# 3d_dsn_approx.net
KiCad netlist of a schematic drawn in Altium Designer
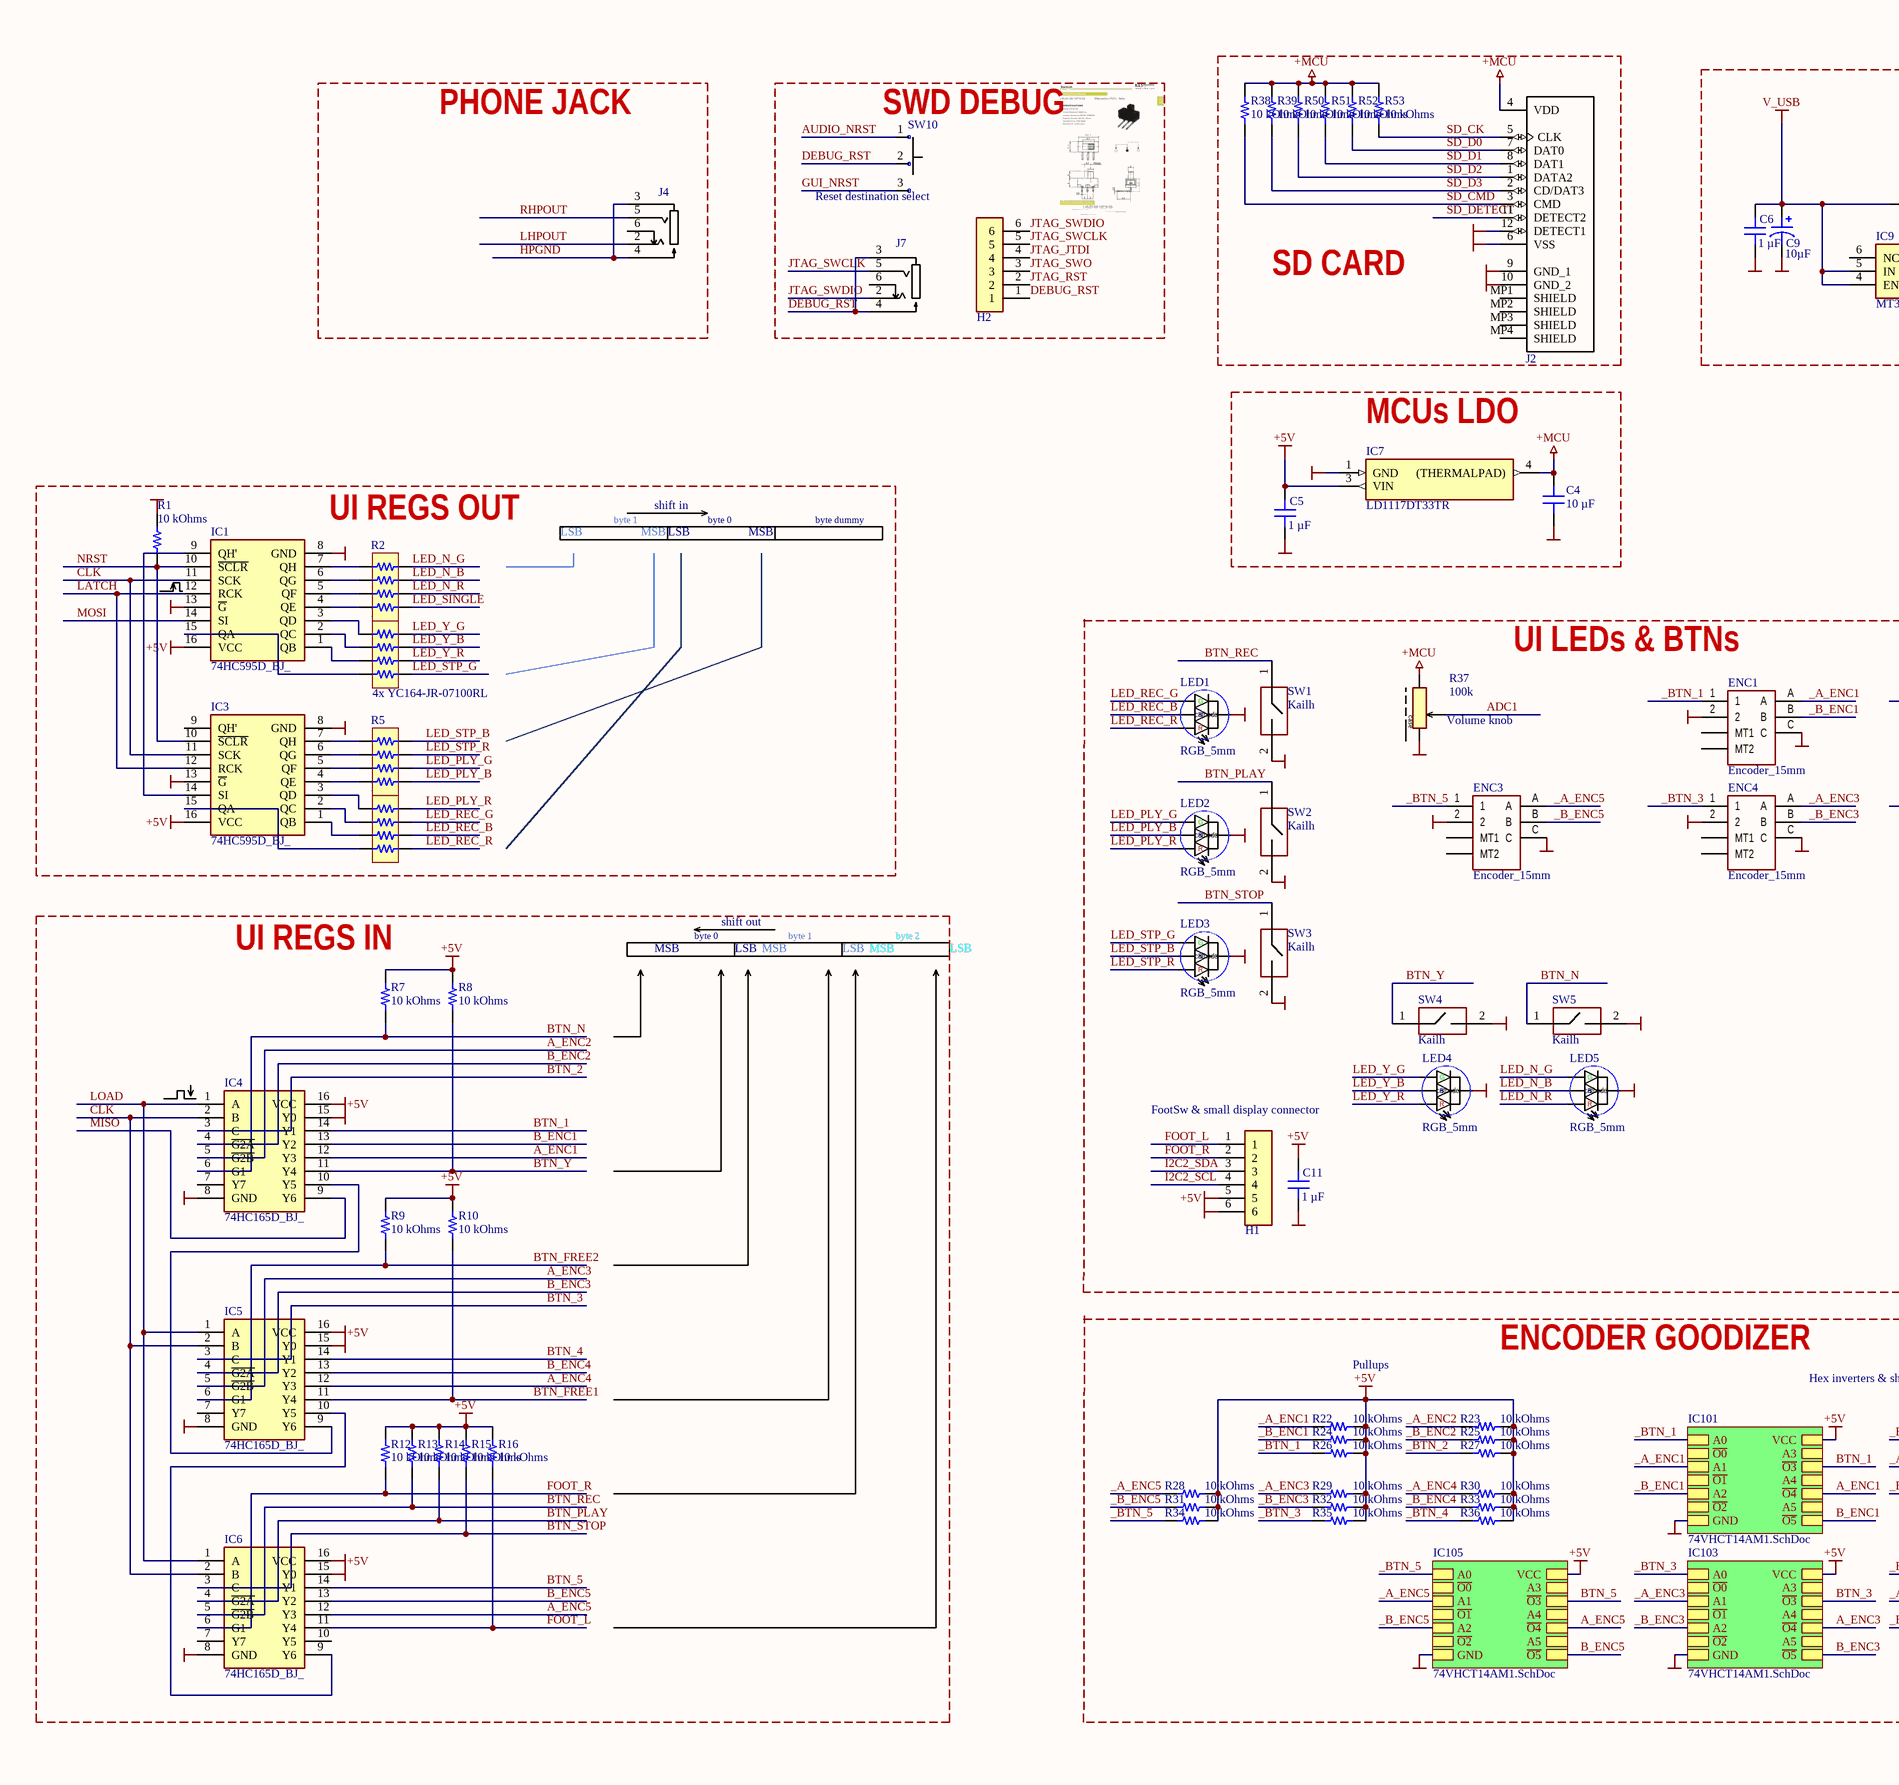
[diagram p0: 3d_dsn_approx.SchDoc, left]
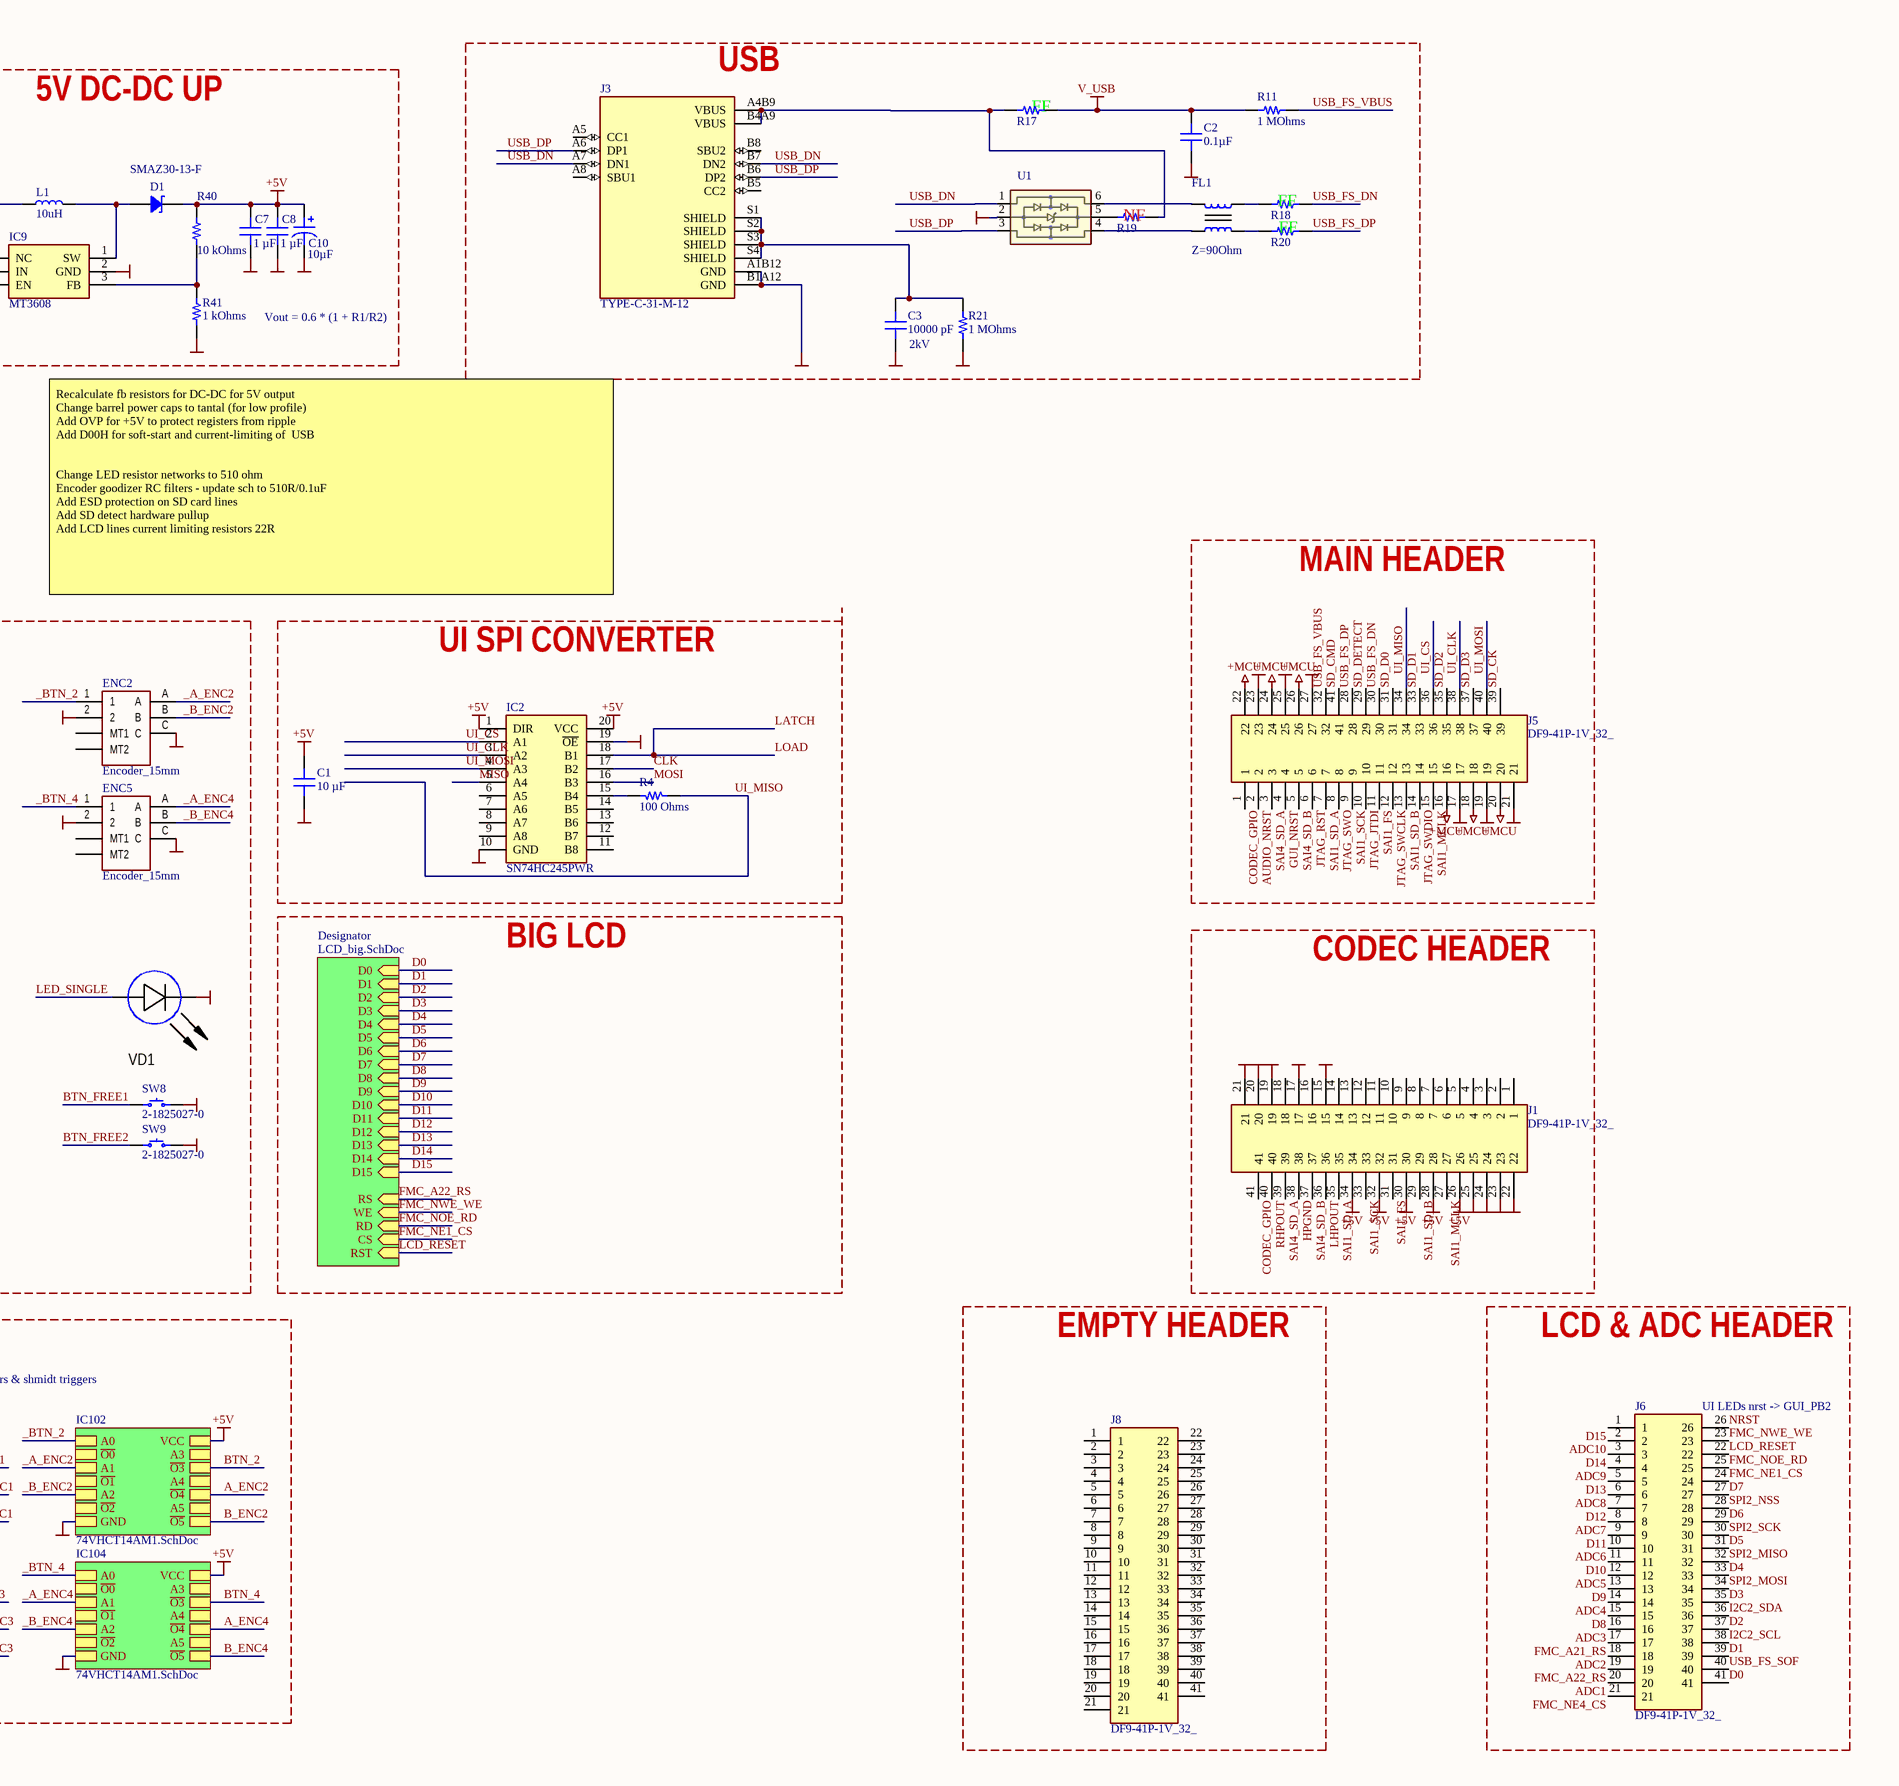
[diagram p1: 3d_dsn_approx.SchDoc, right]

(export (version "E")
  (design (tool "Eeschema 10.0.6"))
  (components
    (comp (ref "C1")
      (value "10 µF")
      (footprint "CAP 0805_2012")
      (description "CAP CER 10UF 10V X5R 0805")
      (fields (field (name "PART NUMBER") "C0805C106K8PAC7800") (field (name "MANUFACTURER") "KEMET"))
      (libsource (lib "Celestial Altium Library - altium_library") (part "Capacitor"))
    )
    (comp (ref "C2")
      (value "0.1µF")
      (footprint "CAP 0402_1005")
      (description "CAP CER 0.1UF 16V X7R 0402")
      (fields (field (name "PART NUMBER") "C0402C104K4RACAUTO") (field (name "MANUFACTURER") "KEMET"))
      (libsource (lib "Celestial Altium Library - altium_library") (part "Capacitor"))
    )
    (comp (ref "C3")
      (value "10000 pF")
      (footprint "CAP 1210_3225 - 1MM")
      (description "CAP CER 10000PF 1KV X7R 1210")
      (fields (field (name "PART NUMBER") "C1210C103KDRAC7800") (field (name "MANUFACTURER") "KEMET"))
      (libsource (lib "Celestial Altium Library - altium_library") (part "Capacitor"))
    )
    (comp (ref "C4")
      (value "10 µF")
      (footprint "CAP 0805_2012")
      (description "CAP CER 10UF 10V X5R 0805")
      (fields (field (name "PART NUMBER") "C0805C106K8PAC7800") (field (name "MANUFACTURER") "KEMET"))
      (libsource (lib "Celestial Altium Library - altium_library") (part "Capacitor"))
    )
    (comp (ref "C5")
      (value "1 µF")
      (footprint "CAP 0805_2012")
      (description "CAP CER 1UF 16V X7R 0805")
      (fields (field (name "PART NUMBER") "C0805C105K4RAC7800") (field (name "MANUFACTURER") "KEMET"))
      (libsource (lib "Celestial Altium Library - altium_library") (part "Capacitor"))
    )
    (comp (ref "C6")
      (value "1 µF")
      (footprint "CAP 0805_2012")
      (description "CAP CER 1UF 16V X7R 0805")
      (fields (field (name "PART NUMBER") "C0805C105K4RAC7800") (field (name "MANUFACTURER") "KEMET"))
      (libsource (lib "Celestial Altium Library - altium_library") (part "Capacitor"))
    )
    (comp (ref "C7")
      (value "1 µF")
      (footprint "CAP 0805_2012")
      (description "CAP CER 1UF 16V X7R 0805")
      (fields (field (name "PART NUMBER") "C0805C105K4RAC7800") (field (name "MANUFACTURER") "KEMET"))
      (libsource (lib "Celestial Altium Library - altium_library") (part "Capacitor"))
    )
    (comp (ref "C8")
      (value "1 µF")
      (footprint "CAP 0805_2012")
      (description "CAP CER 1UF 16V X7R 0805")
      (fields (field (name "PART NUMBER") "C0805C105K4RAC7800") (field (name "MANUFACTURER") "KEMET"))
      (libsource (lib "Celestial Altium Library - altium_library") (part "Capacitor"))
    )
    (comp (ref "C9")
      (value "10µF")
      (footprint "CAP ALSMD POLY 4.3MM H5.5MM")
      (description "CAP ALUM 10UF 20% 35V SMD")
      (fields
        (field (name "PART NUMBER") "EEE-1VA100WR")
        (field (name "MANUFACTURER") "Panasonic Electronic Components")
      )
      (libsource (lib "Celestial Altium Library - altium_library") (part "Polarised Capacitor"))
    )
    (comp (ref "C10")
      (value "10µF")
      (footprint "CAP ALSMD POLY 4.3MM H5.5MM")
      (description "CAP ALUM 10UF 20% 35V SMD")
      (fields
        (field (name "PART NUMBER") "EEE-1VA100WR")
        (field (name "MANUFACTURER") "Panasonic Electronic Components")
      )
      (libsource (lib "Celestial Altium Library - altium_library") (part "Polarised Capacitor"))
    )
    (comp (ref "C11")
      (value "1 µF")
      (footprint "CAP 0805_2012")
      (description "CAP CER 1UF 16V X7R 0805")
      (fields (field (name "PART NUMBER") "C0805C105K4RAC7800") (field (name "MANUFACTURER") "KEMET"))
      (libsource (lib "Celestial Altium Library - altium_library") (part "Capacitor"))
    )
    (comp (ref "D1")
      (value "SMAZ30-13-F")
      (footprint "DO214AC SMA")
      (description "DIODE ZENER 30V 1W SMA")
      (fields (field (name "MANUFACTURER") "Diodes Incorporated") (field (name "TOLERANCE") "±5%"))
      (libsource (lib "Celestial Altium Library - altium_library") (part "Diode Zener"))
    )
    (comp (ref "ENC1")
      (value "Encoder_15mm")
      (footprint "ProtoStack_H750VBT:EC11_15mm")
      (libsource (lib "ProtoStack_H750VBT") (part "Encoder_15mm"))
    )
    (comp (ref "ENC2")
      (value "Encoder_15mm")
      (footprint "ProtoStack_H750VBT:EC11_15mm")
      (libsource (lib "ProtoStack_H750VBT") (part "Encoder_15mm"))
    )
    (comp (ref "ENC3")
      (value "Encoder_15mm")
      (footprint "ProtoStack_H750VBT:EC11_15mm")
      (libsource (lib "ProtoStack_H750VBT") (part "Encoder_15mm"))
    )
    (comp (ref "ENC4")
      (value "Encoder_15mm")
      (footprint "ProtoStack_H750VBT:EC11_15mm")
      (libsource (lib "ProtoStack_H750VBT") (part "Encoder_15mm"))
    )
    (comp (ref "ENC5")
      (value "Encoder_15mm")
      (footprint "ProtoStack_H750VBT:EC11_15mm")
      (libsource (lib "ProtoStack_H750VBT") (part "Encoder_15mm"))
    )
    (comp (ref "FL1")
      (value "Z=90Ohm")
      (footprint "ProtoStack_H750VBT:FIL_ACM2012-361-2P-T002")
      (description "ACM Series 0805 360 Ohm 220mA 500 mOhm DCR 50 V SMT Common Mode Filter")
      (fields (field (name "MP") "ACM2012-361-2P-T002") (field (name "MF") "TDK"))
      (libsource (lib "ProtoStack_H750VBT") (part "ACM2012-361-2P-T002"))
    )
    (comp (ref "H1")
      (value "1.5-6A")
      (footprint "ProtoStack_H750VBT:1.5-6A")
      (description "Pin Header p=1.5mm, 6 pins")
      (libsource (lib "ProtoStack_H750VBT") (part "1.5-6A"))
    )
    (comp (ref "H2")
      (value "1.5-6A")
      (footprint "ProtoStack_H750VBT:1.5-6A")
      (description "Pin Header p=1.5mm, 6 pins")
      (libsource (lib "") (part "1.5-6A_1"))
    )
    (comp (ref "IC1")
      (value "74HC595D_BJ_")
      (footprint "ProtoStack_H750VBT:SOIC127P600X175-16N")
      (description "Integrated Circuit")
      (fields
        (field (name "MANUFACTURER_PART_NUMBER") "74HC595D(BJ)")
        (field (name "MOUSER PART NUMBER") "757-74HC595DBJ")
      )
      (libsource (lib "ProtoStack_H750VBT") (part "74HC595D_BJ_"))
    )
    (comp (ref "IC2")
      (value "SN74HC245PWR")
      (footprint "ProtoStack_H750VBT:SOP65P640X120-20N")
      (description "Integrated Circuit")
      (fields (field (name "MOUSER PART NUMBER") "595-SN74HC245PWR"))
      (libsource (lib "ProtoStack_H750VBT") (part "SN74HC245PWR"))
    )
    (comp (ref "IC3")
      (value "74HC595D_BJ_")
      (footprint "ProtoStack_H750VBT:SOIC127P600X175-16N")
      (description "Integrated Circuit")
      (fields
        (field (name "MANUFACTURER_PART_NUMBER") "74HC595D(BJ)")
        (field (name "MOUSER PART NUMBER") "757-74HC595DBJ")
      )
      (libsource (lib "ProtoStack_H750VBT") (part "74HC595D_BJ_"))
    )
    (comp (ref "IC4")
      (value "74HC165D_BJ_")
      (footprint "ProtoStack_H750VBT:SOIC127P600X175-16N")
      (description "Integrated Circuit")
      (fields
        (field (name "MANUFACTURER_PART_NUMBER") "74HC165D(BJ)")
        (field (name "MOUSER PART NUMBER") "757-74HC165DBJ")
      )
      (libsource (lib "ProtoStack_H750VBT") (part "74HC165D_BJ_"))
    )
    (comp (ref "IC5")
      (value "74HC165D_BJ_")
      (footprint "ProtoStack_H750VBT:SOIC127P600X175-16N")
      (description "Integrated Circuit")
      (fields
        (field (name "MANUFACTURER_PART_NUMBER") "74HC165D(BJ)")
        (field (name "MOUSER PART NUMBER") "757-74HC165DBJ")
      )
      (libsource (lib "ProtoStack_H750VBT") (part "74HC165D_BJ_"))
    )
    (comp (ref "IC6")
      (value "74HC165D_BJ_")
      (footprint "ProtoStack_H750VBT:SOIC127P600X175-16N")
      (description "Integrated Circuit")
      (fields
        (field (name "MANUFACTURER_PART_NUMBER") "74HC165D(BJ)")
        (field (name "MOUSER PART NUMBER") "757-74HC165DBJ")
      )
      (libsource (lib "ProtoStack_H750VBT") (part "74HC165D_BJ_"))
    )
    (comp (ref "IC7")
      (value "LD1117DT33TR")
      (footprint "ProtoStack_H750VBT:TO228P972X240-3N")
      (description "Integrated Circuit")
      (fields (field (name "MOUSER PART NUMBER") "511-LD1117DT33-TR"))
      (libsource (lib "ProtoStack_H750VBT") (part "LD1117DT33TR"))
    )
    (comp (ref "IC9")
      (value "MT3608")
      (footprint "SamacSys:SOT95P280X145-6N")
      (description "Integrated Circuit")
      (libsource (lib "*") (part "MT3608"))
    )
    (comp (ref "J1")
      (value "DF9-41P-1V_32_")
      (footprint "HIROSE_DF9-41P-1V(32)")
      (description "Connector")
      (fields
        (field (name "MANUFACTURER_PART_NUMBER") "DF9-41P-1V(32)")
        (field (name "MOUSER PART NUMBER") "798-DF9-41P-1V32")
      )
      (libsource (lib "") (part "DF9-41P-1V_32__2"))
    )
    (comp (ref "J2")
      (value "SCHA4B0400")
      (footprint "ProtoStack_H750VBT:SCHA4B0400")
      (description "SD card Connector")
      (fields (field (name "MOUSER PART NUMBER") "688-SCHA4B0400"))
      (libsource (lib "ProtoStack_H750VBT") (part "SCHA4B0400"))
    )
    (comp (ref "J3")
      (value "TYPE-C-31-M-12")
      (footprint "ProtoStack_H750VBT:HRO_TYPE-C-31-M-12 - REZONIT")
      (description "USB Connectors 24 Receptacle 1 8.94*7.3mm RoHS")
      (fields (field (name "MF") "{'manufacturer': u'HRO Electronics Co., Ltd.'}"))
      (libsource (lib "ProtoStack_H750VBT") (part "TYPE-C-31-M-12"))
    )
    (comp (ref "J4")
      (value "35RASMT2BHNTRX")
      (footprint "ProtoStack_H750VBT:PJ_327")
      (description "Conn 3.5MM Stereo Jack F 3 POS Solder RA SMD 3 Terminal 1 Port T/R")
      (fields (field (name "MF") "Switchcraft"))
      (libsource (lib "ProtoStack_H750VBT") (part "3.5mm jack stereo smd"))
    )
    (comp (ref "J5")
      (value "DF9-41P-1V_32_")
      (footprint "ProtoStack_H750VBT:HIROSE_DF9-41P-1V(32)")
      (description "Connector")
      (fields
        (field (name "MANUFACTURER_PART_NUMBER") "DF9-41P-1V(32)")
        (field (name "MOUSER PART NUMBER") "798-DF9-41P-1V32")
      )
      (libsource (lib "ProtoStack_H750VBT") (part "DF9-41P-1V_32_"))
    )
    (comp (ref "J6")
      (value "DF9-41P-1V_32_")
      (footprint "ProtoStack_H750VBT:HIROSE_DF9-41P-1V(32)")
      (description "Connector")
      (fields
        (field (name "MANUFACTURER_PART_NUMBER") "DF9-41P-1V(32)")
        (field (name "MOUSER PART NUMBER") "798-DF9-41P-1V32")
      )
      (libsource (lib "") (part "DF9-41P-1V_32__1"))
    )
    (comp (ref "J7")
      (value "35RASMT2BHNTRX")
      (footprint "ProtoStack_H750VBT:PJ_327")
      (description "Conn 3.5MM Stereo Jack F 3 POS Solder RA SMD 3 Terminal 1 Port T/R")
      (fields (field (name "MF") "Switchcraft"))
      (libsource (lib "ProtoStack_H750VBT") (part "3.5mm jack stereo smd"))
    )
    (comp (ref "J8")
      (value "DF9-41P-1V_32_")
      (footprint "ProtoStack_H750VBT:HIROSE_DF9-41P-1V(32)")
      (description "Connector")
      (fields
        (field (name "MANUFACTURER_PART_NUMBER") "DF9-41P-1V(32)")
        (field (name "MOUSER PART NUMBER") "798-DF9-41P-1V32")
      )
      (libsource (lib "") (part "DF9-41P-1V_32__3"))
    )
    (comp (ref "L1")
      (value "10uH")
      (footprint "ProtoStack_H750VBT:IND_CD54")
      (description "Aliexpress CD54 type inductor")
      (libsource (lib "ProtoStack_H750VBT") (part "Inductor_CD54"))
    )
    (comp (ref "LED1")
      (value "RGB_5mm")
      (footprint "ProtoStack_H750VBT:LED_RGB_5MM")
      (libsource (lib "ProtoStack_H750VBT") (part "RGB_CC_5mm"))
    )
    (comp (ref "LED2")
      (value "RGB_5mm")
      (footprint "ProtoStack_H750VBT:LED_RGB_5MM")
      (libsource (lib "ProtoStack_H750VBT") (part "RGB_CC_5mm"))
    )
    (comp (ref "LED3")
      (value "RGB_5mm")
      (footprint "ProtoStack_H750VBT:LED_RGB_5MM")
      (libsource (lib "ProtoStack_H750VBT") (part "RGB_CC_5mm"))
    )
    (comp (ref "LED4")
      (value "RGB_5mm")
      (footprint "ProtoStack_H750VBT:LED_RGB_5MM")
      (libsource (lib "ProtoStack_H750VBT") (part "RGB_CC_5mm"))
    )
    (comp (ref "LED5")
      (value "RGB_5mm")
      (footprint "ProtoStack_H750VBT:LED_RGB_5MM")
      (libsource (lib "ProtoStack_H750VBT") (part "RGB_CC_5mm"))
    )
    (comp (ref "R1")
      (value "10 kOhms")
      (footprint "RES 0603_1608")
      (description "RES SMD 10K OHM 1% 1/10W 0603")
      (fields (field (name "PART NUMBER") "RT0603FRE0710KL") (field (name "MANUFACTURER") "Yageo"))
      (libsource (lib "Celestial Altium Library - altium_library") (part "Resistor"))
    )
    (comp (ref "R2")
      (value "YC164-JR-07100RL")
      (footprint "RESNET 1206-8 CONVEX")
      (description "RES ARRAY 4 RES 100 OHM 1206")
      (fields (field (name "MANUFACTURER") "Yageo") (field (name "TOLERANCE") "±5%"))
      (libsource (lib "Celestial Altium Library - altium_library") (part "Resistor Array (4 circuit)"))
    )
    (comp (ref "R3")
      (value "YC164-JR-07100RL")
      (footprint "RESNET 1206-8 CONVEX")
      (description "RES ARRAY 4 RES 100 OHM 1206")
      (fields (field (name "MANUFACTURER") "Yageo") (field (name "TOLERANCE") "±5%"))
      (libsource (lib "Celestial Altium Library - altium_library") (part "Resistor Array (4 circuit)"))
    )
    (comp (ref "R4")
      (value "100 Ohms")
      (footprint "RES 0402_1005")
      (description "RES SMD 100 OHM 1% 1/16W 0402")
      (fields (field (name "PART NUMBER") "RT0402FRE07100RL") (field (name "MANUFACTURER") "Yageo"))
      (libsource (lib "Celestial Altium Library - altium_library") (part "Resistor"))
    )
    (comp (ref "R5")
      (value "YC164-JR-07100RL")
      (footprint "RESNET 1206-8 CONVEX")
      (description "RES ARRAY 4 RES 100 OHM 1206")
      (fields (field (name "MANUFACTURER") "Yageo") (field (name "TOLERANCE") "±5%"))
      (libsource (lib "Celestial Altium Library - altium_library") (part "Resistor Array (4 circuit)"))
    )
    (comp (ref "R6")
      (value "YC164-JR-07100RL")
      (footprint "RESNET 1206-8 CONVEX")
      (description "RES ARRAY 4 RES 100 OHM 1206")
      (fields (field (name "MANUFACTURER") "Yageo") (field (name "TOLERANCE") "±5%"))
      (libsource (lib "Celestial Altium Library - altium_library") (part "Resistor Array (4 circuit)"))
    )
    (comp (ref "R7")
      (value "10 kOhms")
      (footprint "RES 0603_1608")
      (description "RES SMD 10K OHM 1% 1/10W 0603")
      (fields (field (name "PART NUMBER") "RT0603FRE0710KL") (field (name "MANUFACTURER") "Yageo"))
      (libsource (lib "Celestial Altium Library - altium_library") (part "Resistor"))
    )
    (comp (ref "R8")
      (value "10 kOhms")
      (footprint "RES 0603_1608")
      (description "RES SMD 10K OHM 1% 1/10W 0603")
      (fields (field (name "PART NUMBER") "RT0603FRE0710KL") (field (name "MANUFACTURER") "Yageo"))
      (libsource (lib "Celestial Altium Library - altium_library") (part "Resistor"))
    )
    (comp (ref "R9")
      (value "10 kOhms")
      (footprint "RES 0603_1608")
      (description "RES SMD 10K OHM 1% 1/10W 0603")
      (fields (field (name "PART NUMBER") "RT0603FRE0710KL") (field (name "MANUFACTURER") "Yageo"))
      (libsource (lib "Celestial Altium Library - altium_library") (part "Resistor"))
    )
    (comp (ref "R10")
      (value "10 kOhms")
      (footprint "RES 0603_1608")
      (description "RES SMD 10K OHM 1% 1/10W 0603")
      (fields (field (name "PART NUMBER") "RT0603FRE0710KL") (field (name "MANUFACTURER") "Yageo"))
      (libsource (lib "Celestial Altium Library - altium_library") (part "Resistor"))
    )
    (comp (ref "R11")
      (value "1 MOhms")
      (footprint "RES 0603_1608")
      (description "RES SMD 1M OHM 1% 1/10W 0603")
      (fields (field (name "PART NUMBER") "RT0603FRE071ML") (field (name "MANUFACTURER") "Yageo"))
      (libsource (lib "Celestial Altium Library - altium_library") (part "Resistor"))
    )
    (comp (ref "R12")
      (value "10 kOhms")
      (footprint "RES 0603_1608")
      (description "RES SMD 10K OHM 1% 1/10W 0603")
      (fields (field (name "PART NUMBER") "RT0603FRE0710KL") (field (name "MANUFACTURER") "Yageo"))
      (libsource (lib "Celestial Altium Library - altium_library") (part "Resistor"))
    )
    (comp (ref "R13")
      (value "10 kOhms")
      (footprint "RES 0603_1608")
      (description "RES SMD 10K OHM 1% 1/10W 0603")
      (fields (field (name "PART NUMBER") "RT0603FRE0710KL") (field (name "MANUFACTURER") "Yageo"))
      (libsource (lib "Celestial Altium Library - altium_library") (part "Resistor"))
    )
    (comp (ref "R14")
      (value "10 kOhms")
      (footprint "RES 0603_1608")
      (description "RES SMD 10K OHM 1% 1/10W 0603")
      (fields (field (name "PART NUMBER") "RT0603FRE0710KL") (field (name "MANUFACTURER") "Yageo"))
      (libsource (lib "Celestial Altium Library - altium_library") (part "Resistor"))
    )
    (comp (ref "R15")
      (value "10 kOhms")
      (footprint "RES 0603_1608")
      (description "RES SMD 10K OHM 1% 1/10W 0603")
      (fields (field (name "PART NUMBER") "RT0603FRE0710KL") (field (name "MANUFACTURER") "Yageo"))
      (libsource (lib "Celestial Altium Library - altium_library") (part "Resistor"))
    )
    (comp (ref "R16")
      (value "10 kOhms")
      (footprint "RES 0603_1608")
      (description "RES SMD 10K OHM 1% 1/10W 0603")
      (fields (field (name "PART NUMBER") "RT0603FRE0710KL") (field (name "MANUFACTURER") "Yageo"))
      (libsource (lib "Celestial Altium Library - altium_library") (part "Resistor"))
    )
    (comp (ref "R17")
      (value "~")
      (footprint "RES 0603_1608")
      (description "RES SMD 0 OHM JUMPER 1/10W 0603")
      (fields (field (name "PART NUMBER") "RCA06030000ZSEA") (field (name "MANUFACTURER") "Vishay Dale"))
      (libsource (lib "Celestial Altium Library - altium_library") (part "Resistor"))
    )
    (comp (ref "R18")
      (value "~")
      (footprint "RES 0603_1608")
      (description "RES SMD 0 OHM JUMPER 1/10W 0603")
      (fields (field (name "PART NUMBER") "RCA06030000ZSEA") (field (name "MANUFACTURER") "Vishay Dale"))
      (libsource (lib "Celestial Altium Library - altium_library") (part "Resistor"))
    )
    (comp (ref "R19")
      (value "~")
      (footprint "RES 0603_1608")
      (description "RES SMD 0 OHM JUMPER 1/10W 0603")
      (fields (field (name "PART NUMBER") "RCA06030000ZSEA") (field (name "MANUFACTURER") "Vishay Dale"))
      (libsource (lib "Celestial Altium Library - altium_library") (part "Resistor"))
    )
    (comp (ref "R20")
      (value "~")
      (footprint "RES 0603_1608")
      (description "RES SMD 0 OHM JUMPER 1/10W 0603")
      (fields (field (name "PART NUMBER") "RCA06030000ZSEA") (field (name "MANUFACTURER") "Vishay Dale"))
      (libsource (lib "Celestial Altium Library - altium_library") (part "Resistor"))
    )
    (comp (ref "R21")
      (value "1 MOhms")
      (footprint "RES 0603_1608")
      (description "RES SMD 1M OHM 1% 1/10W 0603")
      (fields (field (name "PART NUMBER") "RT0603FRE071ML") (field (name "MANUFACTURER") "Yageo"))
      (libsource (lib "Celestial Altium Library - altium_library") (part "Resistor"))
    )
    (comp (ref "R22")
      (value "10 kOhms")
      (footprint "RES 0603_1608")
      (description "RES SMD 10K OHM 1% 1/10W 0603")
      (fields (field (name "PART NUMBER") "RT0603FRE0710KL") (field (name "MANUFACTURER") "Yageo"))
      (libsource (lib "Celestial Altium Library - altium_library") (part "Resistor"))
    )
    (comp (ref "R23")
      (value "10 kOhms")
      (footprint "RES 0603_1608")
      (description "RES SMD 10K OHM 1% 1/10W 0603")
      (fields (field (name "PART NUMBER") "RT0603FRE0710KL") (field (name "MANUFACTURER") "Yageo"))
      (libsource (lib "Celestial Altium Library - altium_library") (part "Resistor"))
    )
    (comp (ref "R24")
      (value "10 kOhms")
      (footprint "RES 0603_1608")
      (description "RES SMD 10K OHM 1% 1/10W 0603")
      (fields (field (name "PART NUMBER") "RT0603FRE0710KL") (field (name "MANUFACTURER") "Yageo"))
      (libsource (lib "Celestial Altium Library - altium_library") (part "Resistor"))
    )
    (comp (ref "R25")
      (value "10 kOhms")
      (footprint "RES 0603_1608")
      (description "RES SMD 10K OHM 1% 1/10W 0603")
      (fields (field (name "PART NUMBER") "RT0603FRE0710KL") (field (name "MANUFACTURER") "Yageo"))
      (libsource (lib "Celestial Altium Library - altium_library") (part "Resistor"))
    )
    (comp (ref "R26")
      (value "10 kOhms")
      (footprint "RES 0603_1608")
      (description "RES SMD 10K OHM 1% 1/10W 0603")
      (fields (field (name "PART NUMBER") "RT0603FRE0710KL") (field (name "MANUFACTURER") "Yageo"))
      (libsource (lib "Celestial Altium Library - altium_library") (part "Resistor"))
    )
    (comp (ref "R27")
      (value "10 kOhms")
      (footprint "RES 0603_1608")
      (description "RES SMD 10K OHM 1% 1/10W 0603")
      (fields (field (name "PART NUMBER") "RT0603FRE0710KL") (field (name "MANUFACTURER") "Yageo"))
      (libsource (lib "Celestial Altium Library - altium_library") (part "Resistor"))
    )
    (comp (ref "R28")
      (value "10 kOhms")
      (footprint "RES 0603_1608")
      (description "RES SMD 10K OHM 1% 1/10W 0603")
      (fields (field (name "PART NUMBER") "RT0603FRE0710KL") (field (name "MANUFACTURER") "Yageo"))
      (libsource (lib "Celestial Altium Library - altium_library") (part "Resistor"))
    )
    (comp (ref "R29")
      (value "10 kOhms")
      (footprint "RES 0603_1608")
      (description "RES SMD 10K OHM 1% 1/10W 0603")
      (fields (field (name "PART NUMBER") "RT0603FRE0710KL") (field (name "MANUFACTURER") "Yageo"))
      (libsource (lib "Celestial Altium Library - altium_library") (part "Resistor"))
    )
    (comp (ref "R30")
      (value "10 kOhms")
      (footprint "RES 0603_1608")
      (description "RES SMD 10K OHM 1% 1/10W 0603")
      (fields (field (name "PART NUMBER") "RT0603FRE0710KL") (field (name "MANUFACTURER") "Yageo"))
      (libsource (lib "Celestial Altium Library - altium_library") (part "Resistor"))
    )
    (comp (ref "R31")
      (value "10 kOhms")
      (footprint "RES 0603_1608")
      (description "RES SMD 10K OHM 1% 1/10W 0603")
      (fields (field (name "PART NUMBER") "RT0603FRE0710KL") (field (name "MANUFACTURER") "Yageo"))
      (libsource (lib "Celestial Altium Library - altium_library") (part "Resistor"))
    )
    (comp (ref "R32")
      (value "10 kOhms")
      (footprint "RES 0603_1608")
      (description "RES SMD 10K OHM 1% 1/10W 0603")
      (fields (field (name "PART NUMBER") "RT0603FRE0710KL") (field (name "MANUFACTURER") "Yageo"))
      (libsource (lib "Celestial Altium Library - altium_library") (part "Resistor"))
    )
    (comp (ref "R33")
      (value "10 kOhms")
      (footprint "RES 0603_1608")
      (description "RES SMD 10K OHM 1% 1/10W 0603")
      (fields (field (name "PART NUMBER") "RT0603FRE0710KL") (field (name "MANUFACTURER") "Yageo"))
      (libsource (lib "Celestial Altium Library - altium_library") (part "Resistor"))
    )
    (comp (ref "R34")
      (value "10 kOhms")
      (footprint "RES 0603_1608")
      (description "RES SMD 10K OHM 1% 1/10W 0603")
      (fields (field (name "PART NUMBER") "RT0603FRE0710KL") (field (name "MANUFACTURER") "Yageo"))
      (libsource (lib "Celestial Altium Library - altium_library") (part "Resistor"))
    )
    (comp (ref "R35")
      (value "10 kOhms")
      (footprint "RES 0603_1608")
      (description "RES SMD 10K OHM 1% 1/10W 0603")
      (fields (field (name "PART NUMBER") "RT0603FRE0710KL") (field (name "MANUFACTURER") "Yageo"))
      (libsource (lib "Celestial Altium Library - altium_library") (part "Resistor"))
    )
    (comp (ref "R36")
      (value "10 kOhms")
      (footprint "RES 0603_1608")
      (description "RES SMD 10K OHM 1% 1/10W 0603")
      (fields (field (name "PART NUMBER") "RT0603FRE0710KL") (field (name "MANUFACTURER") "Yageo"))
      (libsource (lib "Celestial Altium Library - altium_library") (part "Resistor"))
    )
    (comp (ref "R37") (value "100k") (footprint "POT") (libsource (lib "Analog") (part "POT 9MM 100K")))
    (comp (ref "R38")
      (value "10 kOhms")
      (footprint "RES 0603_1608")
      (description "RES SMD 10K OHM 1% 1/10W 0603")
      (fields (field (name "PART NUMBER") "RT0603FRE0710KL") (field (name "MANUFACTURER") "Yageo"))
      (libsource (lib "Celestial Altium Library - altium_library") (part "Resistor"))
    )
    (comp (ref "R39")
      (value "10 kOhms")
      (footprint "RES 0603_1608")
      (description "RES SMD 10K OHM 1% 1/10W 0603")
      (fields (field (name "PART NUMBER") "RT0603FRE0710KL") (field (name "MANUFACTURER") "Yageo"))
      (libsource (lib "Celestial Altium Library - altium_library") (part "Resistor"))
    )
    (comp (ref "R40")
      (value "10 kOhms")
      (footprint "RES 0603_1608")
      (description "RES SMD 10K OHM 1% 1/10W 0603")
      (fields (field (name "PART NUMBER") "RT0603FRE0710KL") (field (name "MANUFACTURER") "Yageo"))
      (libsource (lib "Celestial Altium Library - altium_library") (part "Resistor"))
    )
    (comp (ref "R41")
      (value "1 kOhms")
      (footprint "RES 0603_1608")
      (description "RES SMD 1K OHM 1% 1/10W 0603")
      (fields (field (name "PART NUMBER") "RT0603FRE071KL") (field (name "MANUFACTURER") "Yageo"))
      (libsource (lib "Celestial Altium Library - altium_library") (part "Resistor"))
    )
    (comp (ref "R50")
      (value "10 kOhms")
      (footprint "RES 0603_1608")
      (description "RES SMD 10K OHM 1% 1/10W 0603")
      (fields (field (name "PART NUMBER") "RT0603FRE0710KL") (field (name "MANUFACTURER") "Yageo"))
      (libsource (lib "Celestial Altium Library - altium_library") (part "Resistor"))
    )
    (comp (ref "R51")
      (value "10 kOhms")
      (footprint "RES 0603_1608")
      (description "RES SMD 10K OHM 1% 1/10W 0603")
      (fields (field (name "PART NUMBER") "RT0603FRE0710KL") (field (name "MANUFACTURER") "Yageo"))
      (libsource (lib "Celestial Altium Library - altium_library") (part "Resistor"))
    )
    (comp (ref "R52")
      (value "10 kOhms")
      (footprint "RES 0603_1608")
      (description "RES SMD 10K OHM 1% 1/10W 0603")
      (fields (field (name "PART NUMBER") "RT0603FRE0710KL") (field (name "MANUFACTURER") "Yageo"))
      (libsource (lib "Celestial Altium Library - altium_library") (part "Resistor"))
    )
    (comp (ref "R53")
      (value "10 kOhms")
      (footprint "RES 0603_1608")
      (description "RES SMD 10K OHM 1% 1/10W 0603")
      (fields (field (name "PART NUMBER") "RT0603FRE0710KL") (field (name "MANUFACTURER") "Yageo"))
      (libsource (lib "Celestial Altium Library - altium_library") (part "Resistor"))
    )
    (comp (ref "SW1")
      (value "Kailh")
      (footprint "ProtoStack_H750VBT:Kailh_Low")
      (description "Kailh keyboard switch")
      (libsource (lib "ProtoStack_H750VBT") (part "Kailh_SW"))
    )
    (comp (ref "SW2")
      (value "Kailh")
      (footprint "ProtoStack_H750VBT:Kailh_Low")
      (description "Kailh keyboard switch")
      (libsource (lib "ProtoStack_H750VBT") (part "Kailh_SW"))
    )
    (comp (ref "SW3")
      (value "Kailh")
      (footprint "ProtoStack_H750VBT:Kailh_Low")
      (description "Kailh keyboard switch")
      (libsource (lib "ProtoStack_H750VBT") (part "Kailh_SW"))
    )
    (comp (ref "SW4")
      (value "Kailh")
      (footprint "ProtoStack_H750VBT:Kailh_Low")
      (description "Kailh keyboard switch")
      (libsource (lib "") (part "Kailh_SW_1"))
    )
    (comp (ref "SW5")
      (value "Kailh")
      (footprint "ProtoStack_H750VBT:Kailh_Low")
      (description "Kailh keyboard switch")
      (libsource (lib "") (part "Kailh_SW_1"))
    )
    (comp (ref "SW8")
      (value "2-1825027-0")
      (footprint "TE 2-1825027-0")
      (description "SWITCH TACTILE SPST-NO 0.05A 24V")
      (fields (field (name "MANUFACTURER") "TE Connectivity ALCOSWITCH Switches"))
      (libsource (lib "Celestial Altium Library - altium_library") (part "SPST-NO 2 PIN"))
    )
    (comp (ref "SW9")
      (value "2-1825027-0")
      (footprint "TE 2-1825027-0")
      (description "SWITCH TACTILE SPST-NO 0.05A 24V")
      (fields (field (name "MANUFACTURER") "TE Connectivity ALCOSWITCH Switches"))
      (libsource (lib "Celestial Altium Library - altium_library") (part "SPST-NO 2 PIN"))
    )
    (comp (ref "SW10")
      (value "Reset destination select")
      (footprint "ProtoStack_H750VBT:SLIDE_SW_BIG")
      (description "Slide switch")
      (libsource (lib "ProtoStack_H750VBT") (part "RockerSwitch_3mm"))
    )
    (comp (ref "U1")
      (value "~")
      (footprint "SOT-666")
      (description "Very Low Capacitance Esd Protection")
      (fields (field (name "MP") "USBLC6-2") (field (name "MF") "STMicroelectronics"))
      (libsource (lib "ProtoStack_H750VBT") (part "USBLC6-2"))
    )
    (comp (ref "VD1")
      (value "~")
      (footprint "LED: 0805R")
      (fields (field (name "VALUEMANUFACTURERPARTNUMBER") "LED, Green, *, *, *, -55...+150°C"))
      (libsource (lib "diode") (part "LED_single"))
    )
  )
  (nets
    (net (code "1") (name "+5V") (class "Default")
      (node (ref "C1") (pin "2") (pinfunction "2_2") (pintype "passive"))
      (node (ref "C10") (pin "1") (pinfunction "1_1") (pintype "passive"))
      (node (ref "C11") (pin "2") (pinfunction "2_2") (pintype "passive"))
      (node (ref "C5") (pin "2") (pinfunction "2_2") (pintype "passive"))
      (node (ref "C7") (pin "2") (pinfunction "2_2") (pintype "passive"))
      (node (ref "C8") (pin "2") (pinfunction "2_2") (pintype "passive"))
      (node (ref "D1") (pin "2") (pinfunction "2_2") (pintype "passive"))
      (node (ref "H1") (pin "5") (pinfunction "5_5") (pintype "passive"))
      (node (ref "IC1") (pin "16") (pinfunction "VCC_16") (pintype "passive"))
      (node (ref "IC2") (pin "1") (pinfunction "DIR_1") (pintype "passive"))
      (node (ref "IC2") (pin "20") (pinfunction "VCC_20") (pintype "passive"))
      (node (ref "IC3") (pin "16") (pinfunction "VCC_16") (pintype "passive"))
      (node (ref "IC4") (pin "16") (pinfunction "VCC_16") (pintype "passive"))
      (node (ref "IC5") (pin "16") (pinfunction "VCC_16") (pintype "passive"))
      (node (ref "IC6") (pin "16") (pinfunction "VCC_16") (pintype "passive"))
      (node (ref "IC7") (pin "3") (pinfunction "VIN_3") (pintype "output"))
      (node (ref "J1") (pin "26") (pinfunction "26_26") (pintype "passive"))
      (node (ref "J1") (pin "28") (pinfunction "28_28") (pintype "passive"))
      (node (ref "J1") (pin "30") (pinfunction "30_30") (pintype "passive"))
      (node (ref "J1") (pin "32") (pinfunction "32_32") (pintype "passive"))
      (node (ref "J1") (pin "34") (pinfunction "34_34") (pintype "passive"))
      (node (ref "R10") (pin "2") (pinfunction "2_2") (pintype "passive"))
      (node (ref "R12") (pin "2") (pinfunction "2_2") (pintype "passive"))
      (node (ref "R13") (pin "2") (pinfunction "2_2") (pintype "passive"))
      (node (ref "R14") (pin "2") (pinfunction "2_2") (pintype "passive"))
      (node (ref "R15") (pin "2") (pinfunction "2_2") (pintype "passive"))
      (node (ref "R16") (pin "2") (pinfunction "2_2") (pintype "passive"))
      (node (ref "R22") (pin "2") (pinfunction "2_2") (pintype "passive"))
      (node (ref "R23") (pin "2") (pinfunction "2_2") (pintype "passive"))
      (node (ref "R24") (pin "2") (pinfunction "2_2") (pintype "passive"))
      (node (ref "R25") (pin "2") (pinfunction "2_2") (pintype "passive"))
      (node (ref "R26") (pin "2") (pinfunction "2_2") (pintype "passive"))
      (node (ref "R27") (pin "2") (pinfunction "2_2") (pintype "passive"))
      (node (ref "R28") (pin "2") (pinfunction "2_2") (pintype "passive"))
      (node (ref "R29") (pin "2") (pinfunction "2_2") (pintype "passive"))
      (node (ref "R30") (pin "2") (pinfunction "2_2") (pintype "passive"))
      (node (ref "R31") (pin "2") (pinfunction "2_2") (pintype "passive"))
      (node (ref "R32") (pin "2") (pinfunction "2_2") (pintype "passive"))
      (node (ref "R33") (pin "2") (pinfunction "2_2") (pintype "passive"))
      (node (ref "R34") (pin "2") (pinfunction "2_2") (pintype "passive"))
      (node (ref "R35") (pin "2") (pinfunction "2_2") (pintype "passive"))
      (node (ref "R36") (pin "2") (pinfunction "2_2") (pintype "passive"))
      (node (ref "R40") (pin "2") (pinfunction "2_2") (pintype "passive"))
      (node (ref "R7") (pin "2") (pinfunction "2_2") (pintype "passive"))
      (node (ref "R8") (pin "2") (pinfunction "2_2") (pintype "passive"))
      (node (ref "R9") (pin "2") (pinfunction "2_2") (pintype "passive"))
    )
    (net (code "2") (name "+MCU") (class "Default")
      (node (ref "C4") (pin "2") (pinfunction "2_2") (pintype "passive"))
      (node (ref "IC7") (pin "4") (pinfunction "(THERMALPAD)_4") (pintype "output"))
      (node (ref "J2") (pin "4") (pinfunction "VDD_4") (pintype "power_in"))
      (node (ref "J5") (pin "16") (pinfunction "16_16") (pintype "passive"))
      (node (ref "J5") (pin "18") (pinfunction "18_18") (pintype "passive"))
      (node (ref "J5") (pin "20") (pinfunction "20_20") (pintype "passive"))
      (node (ref "J5") (pin "22") (pinfunction "22_22") (pintype "passive"))
      (node (ref "J5") (pin "24") (pinfunction "24_24") (pintype "passive"))
      (node (ref "J5") (pin "26") (pinfunction "26_26") (pintype "passive"))
      (node (ref "R37") (pin "1") (pinfunction "1_1") (pintype "passive"))
      (node (ref "R38") (pin "2") (pinfunction "2_2") (pintype "passive"))
      (node (ref "R39") (pin "2") (pinfunction "2_2") (pintype "passive"))
      (node (ref "R50") (pin "2") (pinfunction "2_2") (pintype "passive"))
      (node (ref "R51") (pin "2") (pinfunction "2_2") (pintype "passive"))
      (node (ref "R52") (pin "2") (pinfunction "2_2") (pintype "passive"))
      (node (ref "R53") (pin "2") (pinfunction "2_2") (pintype "passive"))
    )
    (net (code "18") (name "/ADC1") (class "Default")
      (node (ref "J6") (pin "20") (pinfunction "20_20") (pintype "passive"))
      (node (ref "R37") (pin "2") (pinfunction "2_2") (pintype "passive"))
    )
    (net (code "19") (name "/ADC2") (class "Default")
      (node (ref "J6") (pin "18") (pinfunction "18_18") (pintype "passive"))
    )
    (net (code "20") (name "/ADC3") (class "Default")
      (node (ref "J6") (pin "16") (pinfunction "16_16") (pintype "passive"))
    )
    (net (code "21") (name "/ADC4") (class "Default")
      (node (ref "J6") (pin "14") (pinfunction "14_14") (pintype "passive"))
    )
    (net (code "22") (name "/ADC5") (class "Default")
      (node (ref "J6") (pin "12") (pinfunction "12_12") (pintype "passive"))
    )
    (net (code "23") (name "/ADC6") (class "Default")
      (node (ref "J6") (pin "10") (pinfunction "10_10") (pintype "passive"))
    )
    (net (code "24") (name "/ADC7") (class "Default")
      (node (ref "J6") (pin "8") (pinfunction "8_8") (pintype "passive"))
    )
    (net (code "25") (name "/ADC8") (class "Default")
      (node (ref "J6") (pin "6") (pinfunction "6_6") (pintype "passive"))
    )
    (net (code "26") (name "/ADC9") (class "Default")
      (node (ref "J6") (pin "4") (pinfunction "4_4") (pintype "passive"))
    )
    (net (code "27") (name "/ADC10") (class "Default")
      (node (ref "J6") (pin "2") (pinfunction "2_2") (pintype "passive"))
    )
    (net (code "28") (name "/AUDIO_NRST") (class "Default")
      (node (ref "J5") (pin "2") (pinfunction "2_2") (pintype "passive"))
      (node (ref "SW10") (pin "1") (pinfunction "1_1") (pintype "passive"))
    )
    (net (code "29") (name "/A_ENC1") (class "Default")
      (node (ref "IC4") (pin "12") (pinfunction "Y3_12") (pintype "passive"))
    )
    (net (code "30") (name "/A_ENC2") (class "Default")
      (node (ref "IC4") (pin "5") (pinfunction "~{G2B}_5") (pintype "passive"))
    )
    (net (code "31") (name "/A_ENC3") (class "Default")
      (node (ref "IC5") (pin "5") (pinfunction "~{G2B}_5") (pintype "passive"))
    )
    (net (code "32") (name "/A_ENC4") (class "Default")
      (node (ref "IC5") (pin "12") (pinfunction "Y3_12") (pintype "passive"))
    )
    (net (code "33") (name "/A_ENC5") (class "Default")
      (node (ref "IC6") (pin "12") (pinfunction "Y3_12") (pintype "passive"))
    )
    (net (code "34") (name "/BTN_1") (class "Default")
      (node (ref "IC4") (pin "14") (pinfunction "Y1_14") (pintype "passive"))
    )
    (net (code "35") (name "/BTN_2") (class "Default")
      (node (ref "IC4") (pin "3") (pinfunction "C_3") (pintype "passive"))
    )
    (net (code "36") (name "/BTN_3") (class "Default")
      (node (ref "IC5") (pin "3") (pinfunction "C_3") (pintype "passive"))
    )
    (net (code "37") (name "/BTN_4") (class "Default")
      (node (ref "IC5") (pin "14") (pinfunction "Y1_14") (pintype "passive"))
    )
    (net (code "38") (name "/BTN_5") (class "Default")
      (node (ref "IC6") (pin "14") (pinfunction "Y1_14") (pintype "passive"))
    )
    (net (code "39") (name "/BTN_FREE1") (class "Default")
      (node (ref "IC5") (pin "11") (pinfunction "Y4_11") (pintype "passive"))
      (node (ref "R10") (pin "1") (pinfunction "1_1") (pintype "passive"))
      (node (ref "SW8") (pin "1") (pinfunction "1_1") (pintype "passive"))
    )
    (net (code "40") (name "/BTN_FREE2") (class "Default")
      (node (ref "IC5") (pin "6") (pinfunction "G1_6") (pintype "passive"))
      (node (ref "R9") (pin "1") (pinfunction "1_1") (pintype "passive"))
      (node (ref "SW9") (pin "1") (pinfunction "1_1") (pintype "passive"))
    )
    (net (code "41") (name "/BTN_N") (class "Default")
      (node (ref "IC4") (pin "6") (pinfunction "G1_6") (pintype "passive"))
      (node (ref "R7") (pin "1") (pinfunction "1_1") (pintype "passive"))
      (node (ref "SW5") (pin "1") (pinfunction "1_1") (pintype "passive"))
    )
    (net (code "42") (name "/BTN_PLAY") (class "Default")
      (node (ref "IC6") (pin "4") (pinfunction "~{G2A}_4") (pintype "passive"))
      (node (ref "R14") (pin "1") (pinfunction "1_1") (pintype "passive"))
      (node (ref "SW2") (pin "1") (pinfunction "1_1") (pintype "passive"))
    )
    (net (code "43") (name "/BTN_REC") (class "Default")
      (node (ref "IC6") (pin "5") (pinfunction "~{G2B}_5") (pintype "passive"))
      (node (ref "R13") (pin "1") (pinfunction "1_1") (pintype "passive"))
      (node (ref "SW1") (pin "1") (pinfunction "1_1") (pintype "passive"))
    )
    (net (code "44") (name "/BTN_STOP") (class "Default")
      (node (ref "IC6") (pin "3") (pinfunction "C_3") (pintype "passive"))
      (node (ref "R15") (pin "1") (pinfunction "1_1") (pintype "passive"))
      (node (ref "SW3") (pin "1") (pinfunction "1_1") (pintype "passive"))
    )
    (net (code "45") (name "/BTN_Y") (class "Default")
      (node (ref "IC4") (pin "11") (pinfunction "Y4_11") (pintype "passive"))
      (node (ref "R8") (pin "1") (pinfunction "1_1") (pintype "passive"))
      (node (ref "SW4") (pin "1") (pinfunction "1_1") (pintype "passive"))
    )
    (net (code "46") (name "/B_ENC1") (class "Default")
      (node (ref "IC4") (pin "13") (pinfunction "Y2_13") (pintype "passive"))
    )
    (net (code "47") (name "/B_ENC2") (class "Default")
      (node (ref "IC4") (pin "4") (pinfunction "~{G2A}_4") (pintype "passive"))
    )
    (net (code "48") (name "/B_ENC3") (class "Default")
      (node (ref "IC5") (pin "4") (pinfunction "~{G2A}_4") (pintype "passive"))
    )
    (net (code "49") (name "/B_ENC4") (class "Default")
      (node (ref "IC5") (pin "13") (pinfunction "Y2_13") (pintype "passive"))
    )
    (net (code "50") (name "/B_ENC5") (class "Default")
      (node (ref "IC6") (pin "13") (pinfunction "Y2_13") (pintype "passive"))
    )
    (net (code "51") (name "/CLK") (class "Default")
      (node (ref "IC1") (pin "11") (pinfunction "SCK_11") (pintype "passive"))
      (node (ref "IC2") (pin "17") (pinfunction "B2_17") (pintype "passive"))
      (node (ref "IC3") (pin "11") (pinfunction "SCK_11") (pintype "passive"))
      (node (ref "IC4") (pin "2") (pinfunction "B_2") (pintype "passive"))
      (node (ref "IC5") (pin "2") (pinfunction "B_2") (pintype "passive"))
      (node (ref "IC6") (pin "2") (pinfunction "B_2") (pintype "passive"))
    )
    (net (code "52") (name "/CODEC_GPIO") (class "Default")
      (node (ref "J1") (pin "41") (pinfunction "41_41") (pintype "passive"))
      (node (ref "J5") (pin "1") (pinfunction "1_1") (pintype "passive"))
    )
    (net (code "53") (name "/D0") (class "Default")
      (node (ref "J6") (pin "41") (pinfunction "41_41") (pintype "passive"))
    )
    (net (code "54") (name "/D1") (class "Default")
      (node (ref "J6") (pin "39") (pinfunction "39_39") (pintype "passive"))
    )
    (net (code "55") (name "/D2") (class "Default")
      (node (ref "J6") (pin "37") (pinfunction "37_37") (pintype "passive"))
    )
    (net (code "56") (name "/D3") (class "Default")
      (node (ref "J6") (pin "35") (pinfunction "35_35") (pintype "passive"))
    )
    (net (code "57") (name "/D4") (class "Default")
      (node (ref "J6") (pin "33") (pinfunction "33_33") (pintype "passive"))
    )
    (net (code "58") (name "/D5") (class "Default")
      (node (ref "J6") (pin "31") (pinfunction "31_31") (pintype "passive"))
    )
    (net (code "59") (name "/D6") (class "Default")
      (node (ref "J6") (pin "29") (pinfunction "29_29") (pintype "passive"))
    )
    (net (code "60") (name "/D7") (class "Default")
      (node (ref "J6") (pin "27") (pinfunction "27_27") (pintype "passive"))
    )
    (net (code "61") (name "/D8") (class "Default")
      (node (ref "J6") (pin "15") (pinfunction "15_15") (pintype "passive"))
    )
    (net (code "62") (name "/D9") (class "Default")
      (node (ref "J6") (pin "13") (pinfunction "13_13") (pintype "passive"))
    )
    (net (code "63") (name "/D10") (class "Default")
      (node (ref "J6") (pin "11") (pinfunction "11_11") (pintype "passive"))
    )
    (net (code "64") (name "/D11") (class "Default")
      (node (ref "J6") (pin "9") (pinfunction "9_9") (pintype "passive"))
    )
    (net (code "65") (name "/D12") (class "Default")
      (node (ref "J6") (pin "7") (pinfunction "7_7") (pintype "passive"))
    )
    (net (code "66") (name "/D13") (class "Default")
      (node (ref "J6") (pin "5") (pinfunction "5_5") (pintype "passive"))
    )
    (net (code "67") (name "/D14") (class "Default")
      (node (ref "J6") (pin "3") (pinfunction "3_3") (pintype "passive"))
    )
    (net (code "68") (name "/D15") (class "Default")
      (node (ref "J6") (pin "1") (pinfunction "1_1") (pintype "passive"))
    )
    (net (code "69") (name "/DEBUG_RST") (class "Default")
      (node (ref "H2") (pin "1") (pinfunction "1_1") (pintype "passive"))
      (node (ref "J7") (pin "3") (pinfunction "1_3") (pintype "passive"))
      (node (ref "J7") (pin "4") (pinfunction "5_4") (pintype "passive"))
      (node (ref "SW10") (pin "2") (pinfunction "2_2") (pintype "passive"))
    )
    (net (code "70") (name "/FMC_A21_RS") (class "Default")
      (node (ref "J6") (pin "17") (pinfunction "17_17") (pintype "passive"))
    )
    (net (code "71") (name "/FMC_A22_RS") (class "Default")
      (node (ref "J6") (pin "19") (pinfunction "19_19") (pintype "passive"))
    )
    (net (code "72") (name "/FMC_NE1_CS") (class "Default")
      (node (ref "J6") (pin "24") (pinfunction "24_24") (pintype "passive"))
    )
    (net (code "73") (name "/FMC_NE4_CS") (class "Default")
      (node (ref "J6") (pin "21") (pinfunction "21_21") (pintype "passive"))
    )
    (net (code "74") (name "/FMC_NOE_RD") (class "Default")
      (node (ref "J6") (pin "25") (pinfunction "25_25") (pintype "passive"))
    )
    (net (code "75") (name "/FMC_NWE_WE") (class "Default")
      (node (ref "J6") (pin "23") (pinfunction "23_23") (pintype "passive"))
    )
    (net (code "76") (name "/FOOT_L") (class "Default")
      (node (ref "H1") (pin "1") (pinfunction "1_1") (pintype "passive"))
      (node (ref "IC6") (pin "11") (pinfunction "Y4_11") (pintype "passive"))
      (node (ref "R16") (pin "1") (pinfunction "1_1") (pintype "passive"))
    )
    (net (code "77") (name "/FOOT_R") (class "Default")
      (node (ref "H1") (pin "2") (pinfunction "2_2") (pintype "passive"))
      (node (ref "IC6") (pin "6") (pinfunction "G1_6") (pintype "passive"))
      (node (ref "R12") (pin "1") (pinfunction "1_1") (pintype "passive"))
    )
    (net (code "78") (name "/GUI_NRST") (class "Default")
      (node (ref "J5") (pin "4") (pinfunction "4_4") (pintype "passive"))
      (node (ref "SW10") (pin "3") (pinfunction "3_3") (pintype "passive"))
    )
    (net (code "79") (name "/HPGND") (class "Default")
      (node (ref "J1") (pin "38") (pinfunction "38_38") (pintype "passive"))
      (node (ref "J4") (pin "3") (pinfunction "1_3") (pintype "passive"))
      (node (ref "J4") (pin "4") (pinfunction "5_4") (pintype "passive"))
    )
    (net (code "80") (name "/I2C2_SCL") (class "Default")
      (node (ref "H1") (pin "4") (pinfunction "4_4") (pintype "passive"))
      (node (ref "J6") (pin "38") (pinfunction "38_38") (pintype "passive"))
    )
    (net (code "81") (name "/I2C2_SDA") (class "Default")
      (node (ref "H1") (pin "3") (pinfunction "3_3") (pintype "passive"))
      (node (ref "J6") (pin "36") (pinfunction "36_36") (pintype "passive"))
    )
    (net (code "82") (name "/JTAG_JTDI") (class "Default")
      (node (ref "H2") (pin "4") (pinfunction "4_4") (pintype "passive"))
      (node (ref "J5") (pin "10") (pinfunction "10_10") (pintype "passive"))
    )
    (net (code "83") (name "/JTAG_RST") (class "Default")
      (node (ref "H2") (pin "2") (pinfunction "2_2") (pintype "passive"))
      (node (ref "J5") (pin "6") (pinfunction "6_6") (pintype "passive"))
    )
    (net (code "84") (name "/JTAG_SWCLK") (class "Default")
      (node (ref "H2") (pin "5") (pinfunction "5_5") (pintype "passive"))
      (node (ref "J5") (pin "12") (pinfunction "12_12") (pintype "passive"))
      (node (ref "J7") (pin "5") (pinfunction "3_5") (pintype "passive"))
    )
    (net (code "85") (name "/JTAG_SWDIO") (class "Default")
      (node (ref "H2") (pin "6") (pinfunction "6_6") (pintype "passive"))
      (node (ref "J5") (pin "14") (pinfunction "14_14") (pintype "passive"))
      (node (ref "J7") (pin "2") (pinfunction "2_2") (pintype "passive"))
    )
    (net (code "86") (name "/JTAG_SWO") (class "Default")
      (node (ref "H2") (pin "3") (pinfunction "3_3") (pintype "passive"))
      (node (ref "J5") (pin "8") (pinfunction "8_8") (pintype "passive"))
    )
    (net (code "87") (name "/LATCH") (class "Default")
      (node (ref "IC1") (pin "12") (pinfunction "RCK_12") (pintype "passive"))
      (node (ref "IC2") (pin "18") (pinfunction "B1_18") (pintype "passive"))
      (node (ref "IC3") (pin "12") (pinfunction "RCK_12") (pintype "passive"))
      (node (ref "IC4") (pin "1") (pinfunction "A_1") (pintype "passive"))
      (node (ref "IC5") (pin "1") (pinfunction "A_1") (pintype "passive"))
      (node (ref "IC6") (pin "1") (pinfunction "A_1") (pintype "passive"))
    )
    (net (code "88") (name "/LCD_RESET") (class "Default")
      (node (ref "J6") (pin "22") (pinfunction "22_22") (pintype "passive"))
    )
    (net (code "89") (name "/LED_N_B") (class "Default")
      (node (ref "LED5") (pin "2") (pinfunction "B_2") (pintype "passive"))
      (node (ref "R2") (pin "3") (pinfunction "3_3") (pintype "passive"))
    )
    (net (code "90") (name "/LED_N_G") (class "Default")
      (node (ref "LED5") (pin "1") (pinfunction "G_1") (pintype "passive"))
      (node (ref "R2") (pin "4") (pinfunction "4_4") (pintype "passive"))
    )
    (net (code "91") (name "/LED_N_R") (class "Default")
      (node (ref "LED5") (pin "4") (pinfunction "R_4") (pintype "passive"))
      (node (ref "R2") (pin "2") (pinfunction "2_2") (pintype "passive"))
    )
    (net (code "92") (name "/LED_PLY_B") (class "Default")
      (node (ref "LED2") (pin "2") (pinfunction "B_2") (pintype "passive"))
      (node (ref "R5") (pin "1") (pinfunction "1_1") (pintype "passive"))
    )
    (net (code "93") (name "/LED_PLY_G") (class "Default")
      (node (ref "LED2") (pin "1") (pinfunction "G_1") (pintype "passive"))
      (node (ref "R5") (pin "2") (pinfunction "2_2") (pintype "passive"))
    )
    (net (code "94") (name "/LED_PLY_R") (class "Default")
      (node (ref "LED2") (pin "4") (pinfunction "R_4") (pintype "passive"))
      (node (ref "R6") (pin "4") (pinfunction "4_4") (pintype "passive"))
    )
    (net (code "95") (name "/LED_REC_B") (class "Default")
      (node (ref "LED1") (pin "2") (pinfunction "B_2") (pintype "passive"))
      (node (ref "R6") (pin "2") (pinfunction "2_2") (pintype "passive"))
    )
    (net (code "96") (name "/LED_REC_G") (class "Default")
      (node (ref "LED1") (pin "1") (pinfunction "G_1") (pintype "passive"))
      (node (ref "R6") (pin "3") (pinfunction "3_3") (pintype "passive"))
    )
    (net (code "97") (name "/LED_REC_R") (class "Default")
      (node (ref "LED1") (pin "4") (pinfunction "R_4") (pintype "passive"))
      (node (ref "R6") (pin "1") (pinfunction "1_1") (pintype "passive"))
    )
    (net (code "98") (name "/LED_SINGLE") (class "Default")
      (node (ref "R2") (pin "1") (pinfunction "1_1") (pintype "passive"))
      (node (ref "VD1") (pin "1") (pinfunction "A_1") (pintype "passive"))
    )
    (net (code "99") (name "/LED_STP_B") (class "Default")
      (node (ref "LED3") (pin "2") (pinfunction "B_2") (pintype "passive"))
      (node (ref "R5") (pin "4") (pinfunction "4_4") (pintype "passive"))
    )
    (net (code "100") (name "/LED_STP_G") (class "Default")
      (node (ref "LED3") (pin "1") (pinfunction "G_1") (pintype "passive"))
      (node (ref "R3") (pin "1") (pinfunction "1_1") (pintype "passive"))
    )
    (net (code "101") (name "/LED_STP_R") (class "Default")
      (node (ref "LED3") (pin "4") (pinfunction "R_4") (pintype "passive"))
      (node (ref "R5") (pin "3") (pinfunction "3_3") (pintype "passive"))
    )
    (net (code "102") (name "/LED_Y_B") (class "Default")
      (node (ref "LED4") (pin "2") (pinfunction "B_2") (pintype "passive"))
      (node (ref "R3") (pin "3") (pinfunction "3_3") (pintype "passive"))
    )
    (net (code "103") (name "/LED_Y_G") (class "Default")
      (node (ref "LED4") (pin "1") (pinfunction "G_1") (pintype "passive"))
      (node (ref "R3") (pin "4") (pinfunction "4_4") (pintype "passive"))
    )
    (net (code "104") (name "/LED_Y_R") (class "Default")
      (node (ref "LED4") (pin "4") (pinfunction "R_4") (pintype "passive"))
      (node (ref "R3") (pin "2") (pinfunction "2_2") (pintype "passive"))
    )
    (net (code "105") (name "/LHPOUT") (class "Default")
      (node (ref "J1") (pin "36") (pinfunction "36_36") (pintype "passive"))
      (node (ref "J4") (pin "2") (pinfunction "2_2") (pintype "passive"))
    )
    (net (code "106") (name "/MISO") (class "Default")
      (node (ref "IC2") (pin "5") (pinfunction "A4_5") (pintype "passive"))
      (node (ref "IC4") (pin "9") (pinfunction "Y6_9") (pintype "passive"))
    )
    (net (code "107") (name "/MOSI") (class "Default")
      (node (ref "IC1") (pin "14") (pinfunction "SI_14") (pintype "passive"))
      (node (ref "IC2") (pin "16") (pinfunction "B3_16") (pintype "passive"))
    )
    (net (code "108") (name "/NRST") (class "Default")
      (node (ref "IC1") (pin "10") (pinfunction "~{SCLR}_10") (pintype "passive"))
      (node (ref "IC3") (pin "10") (pinfunction "~{SCLR}_10") (pintype "passive"))
      (node (ref "J6") (pin "26") (pinfunction "26_26") (pintype "passive"))
      (node (ref "R1") (pin "1") (pinfunction "1_1") (pintype "passive"))
    )
    (net (code "109") (name "/RHPOUT") (class "Default")
      (node (ref "J1") (pin "40") (pinfunction "40_40") (pintype "passive"))
      (node (ref "J4") (pin "5") (pinfunction "3_5") (pintype "passive"))
    )
    (net (code "110") (name "/SAI1_FS") (class "Default")
      (node (ref "J1") (pin "31") (pinfunction "31_31") (pintype "passive"))
      (node (ref "J5") (pin "11") (pinfunction "11_11") (pintype "passive"))
    )
    (net (code "111") (name "/SAI1_MCLK") (class "Default")
      (node (ref "J1") (pin "27") (pinfunction "27_27") (pintype "passive"))
      (node (ref "J5") (pin "15") (pinfunction "15_15") (pintype "passive"))
    )
    (net (code "112") (name "/SAI1_SCK") (class "Default")
      (node (ref "J1") (pin "33") (pinfunction "33_33") (pintype "passive"))
      (node (ref "J5") (pin "9") (pinfunction "9_9") (pintype "passive"))
    )
    (net (code "113") (name "/SAI1_SD_A") (class "Default")
      (node (ref "J1") (pin "35") (pinfunction "35_35") (pintype "passive"))
      (node (ref "J5") (pin "7") (pinfunction "7_7") (pintype "passive"))
    )
    (net (code "114") (name "/SAI1_SD_B") (class "Default")
      (node (ref "J1") (pin "29") (pinfunction "29_29") (pintype "passive"))
      (node (ref "J5") (pin "13") (pinfunction "13_13") (pintype "passive"))
    )
    (net (code "115") (name "/SAI4_SD_A") (class "Default")
      (node (ref "J1") (pin "39") (pinfunction "39_39") (pintype "passive"))
      (node (ref "J5") (pin "3") (pinfunction "3_3") (pintype "passive"))
    )
    (net (code "116") (name "/SAI4_SD_B") (class "Default")
      (node (ref "J1") (pin "37") (pinfunction "37_37") (pintype "passive"))
      (node (ref "J5") (pin "5") (pinfunction "5_5") (pintype "passive"))
    )
    (net (code "117") (name "/SD_CK") (class "Default")
      (node (ref "J2") (pin "5") (pinfunction "CLK_5") (pintype "bidirectional"))
      (node (ref "J5") (pin "39") (pinfunction "39_39") (pintype "passive"))
      (node (ref "R53") (pin "1") (pinfunction "1_1") (pintype "passive"))
    )
    (net (code "118") (name "/SD_CMD") (class "Default")
      (node (ref "J2") (pin "3") (pinfunction "CMD_3") (pintype "bidirectional"))
      (node (ref "J5") (pin "41") (pinfunction "41_41") (pintype "passive"))
      (node (ref "R38") (pin "1") (pinfunction "1_1") (pintype "passive"))
    )
    (net (code "119") (name "/SD_D0") (class "Default")
      (node (ref "J2") (pin "7") (pinfunction "DAT0_7") (pintype "bidirectional"))
      (node (ref "J5") (pin "31") (pinfunction "31_31") (pintype "passive"))
      (node (ref "R52") (pin "1") (pinfunction "1_1") (pintype "passive"))
    )
    (net (code "120") (name "/SD_D1") (class "Default")
      (node (ref "J2") (pin "8") (pinfunction "DAT1_8") (pintype "bidirectional"))
      (node (ref "J5") (pin "33") (pinfunction "33_33") (pintype "passive"))
      (node (ref "R51") (pin "1") (pinfunction "1_1") (pintype "passive"))
    )
    (net (code "121") (name "/SD_D2") (class "Default")
      (node (ref "J2") (pin "1") (pinfunction "DATA2_1") (pintype "bidirectional"))
      (node (ref "J5") (pin "35") (pinfunction "35_35") (pintype "passive"))
      (node (ref "R50") (pin "1") (pinfunction "1_1") (pintype "passive"))
    )
    (net (code "122") (name "/SD_D3") (class "Default")
      (node (ref "J2") (pin "2") (pinfunction "CD/DAT3_2") (pintype "bidirectional"))
      (node (ref "J5") (pin "37") (pinfunction "37_37") (pintype "passive"))
      (node (ref "R39") (pin "1") (pinfunction "1_1") (pintype "passive"))
    )
    (net (code "123") (name "/SD_DETECT") (class "Default")
      (node (ref "J2") (pin "11") (pinfunction "DETECT2_11") (pintype "bidirectional"))
      (node (ref "J5") (pin "29") (pinfunction "29_29") (pintype "passive"))
    )
    (net (code "124") (name "/SPI2_MISO") (class "Default")
      (node (ref "J6") (pin "32") (pinfunction "32_32") (pintype "passive"))
    )
    (net (code "125") (name "/SPI2_MOSI") (class "Default")
      (node (ref "J6") (pin "34") (pinfunction "34_34") (pintype "passive"))
    )
    (net (code "126") (name "/SPI2_NSS") (class "Default")
      (node (ref "J6") (pin "28") (pinfunction "28_28") (pintype "passive"))
    )
    (net (code "127") (name "/SPI2_SCK") (class "Default")
      (node (ref "J6") (pin "30") (pinfunction "30_30") (pintype "passive"))
    )
    (net (code "128") (name "/UI_CLK") (class "Default")
      (node (ref "IC2") (pin "3") (pinfunction "A2_3") (pintype "passive"))
      (node (ref "J5") (pin "38") (pinfunction "38_38") (pintype "passive"))
    )
    (net (code "129") (name "/UI_CS") (class "Default")
      (node (ref "IC2") (pin "2") (pinfunction "A1_2") (pintype "passive"))
      (node (ref "J5") (pin "36") (pinfunction "36_36") (pintype "passive"))
    )
    (net (code "130") (name "/UI_MISO") (class "Default")
      (node (ref "J5") (pin "34") (pinfunction "34_34") (pintype "passive"))
      (node (ref "R4") (pin "1") (pinfunction "1_1") (pintype "passive"))
    )
    (net (code "131") (name "/UI_MOSI") (class "Default")
      (node (ref "IC2") (pin "4") (pinfunction "A3_4") (pintype "passive"))
      (node (ref "J5") (pin "40") (pinfunction "40_40") (pintype "passive"))
    )
    (net (code "132") (name "/USB_DN") (class "Default")
      (node (ref "J3") (pin "A7") (pinfunction "DN1_A7") (pintype "bidirectional"))
      (node (ref "J3") (pin "B7") (pinfunction "DN2_B7") (pintype "bidirectional"))
      (node (ref "U1") (pin "1") (pinfunction "1_1") (pintype "bidirectional"))
    )
    (net (code "133") (name "/USB_DP") (class "Default")
      (node (ref "J3") (pin "A6") (pinfunction "DP1_A6") (pintype "bidirectional"))
      (node (ref "J3") (pin "B6") (pinfunction "DP2_B6") (pintype "bidirectional"))
      (node (ref "U1") (pin "3") (pinfunction "3_3") (pintype "bidirectional"))
    )
    (net (code "134") (name "/USB_FS_DN") (class "Default")
      (node (ref "J5") (pin "30") (pinfunction "30_30") (pintype "passive"))
      (node (ref "R18") (pin "1") (pinfunction "1_1") (pintype "passive"))
    )
    (net (code "135") (name "/USB_FS_DP") (class "Default")
      (node (ref "J5") (pin "28") (pinfunction "28_28") (pintype "passive"))
      (node (ref "R20") (pin "1") (pinfunction "1_1") (pintype "passive"))
    )
    (net (code "136") (name "/USB_FS_SOF") (class "Default")
      (node (ref "J6") (pin "40") (pinfunction "40_40") (pintype "passive"))
    )
    (net (code "137") (name "/USB_FS_VBUS") (class "Default")
      (node (ref "J5") (pin "32") (pinfunction "32_32") (pintype "passive"))
      (node (ref "R11") (pin "1") (pinfunction "1_1") (pintype "passive"))
    )
    (net (code "138") (name "/_A_ENC1") (class "Default")
      (node (ref "ENC1") (pin "A") (pinfunction "A_A") (pintype "passive"))
      (node (ref "R22") (pin "1") (pinfunction "1_1") (pintype "passive"))
    )
    (net (code "139") (name "/_A_ENC2") (class "Default")
      (node (ref "ENC2") (pin "A") (pinfunction "A_A") (pintype "passive"))
      (node (ref "R23") (pin "1") (pinfunction "1_1") (pintype "passive"))
    )
    (net (code "140") (name "/_A_ENC3") (class "Default")
      (node (ref "ENC4") (pin "A") (pinfunction "A_A") (pintype "passive"))
      (node (ref "R29") (pin "1") (pinfunction "1_1") (pintype "passive"))
    )
    (net (code "141") (name "/_A_ENC4") (class "Default")
      (node (ref "ENC5") (pin "A") (pinfunction "A_A") (pintype "passive"))
      (node (ref "R30") (pin "1") (pinfunction "1_1") (pintype "passive"))
    )
    (net (code "142") (name "/_A_ENC5") (class "Default")
      (node (ref "ENC3") (pin "A") (pinfunction "A_A") (pintype "passive"))
      (node (ref "R28") (pin "1") (pinfunction "1_1") (pintype "passive"))
    )
    (net (code "143") (name "/_BTN_1") (class "Default")
      (node (ref "ENC1") (pin "1") (pinfunction "1_1") (pintype "passive"))
      (node (ref "R26") (pin "1") (pinfunction "1_1") (pintype "passive"))
    )
    (net (code "144") (name "/_BTN_2") (class "Default")
      (node (ref "ENC2") (pin "1") (pinfunction "1_1") (pintype "passive"))
      (node (ref "R27") (pin "1") (pinfunction "1_1") (pintype "passive"))
    )
    (net (code "145") (name "/_BTN_3") (class "Default")
      (node (ref "ENC4") (pin "1") (pinfunction "1_1") (pintype "passive"))
      (node (ref "R35") (pin "1") (pinfunction "1_1") (pintype "passive"))
    )
    (net (code "146") (name "/_BTN_4") (class "Default")
      (node (ref "ENC5") (pin "1") (pinfunction "1_1") (pintype "passive"))
      (node (ref "R36") (pin "1") (pinfunction "1_1") (pintype "passive"))
    )
    (net (code "147") (name "/_BTN_5") (class "Default")
      (node (ref "ENC3") (pin "1") (pinfunction "1_1") (pintype "passive"))
      (node (ref "R34") (pin "1") (pinfunction "1_1") (pintype "passive"))
    )
    (net (code "148") (name "/_B_ENC1") (class "Default")
      (node (ref "ENC1") (pin "B") (pinfunction "B_B") (pintype "passive"))
      (node (ref "R24") (pin "1") (pinfunction "1_1") (pintype "passive"))
    )
    (net (code "149") (name "/_B_ENC2") (class "Default")
      (node (ref "ENC2") (pin "B") (pinfunction "B_B") (pintype "passive"))
      (node (ref "R25") (pin "1") (pinfunction "1_1") (pintype "passive"))
    )
    (net (code "150") (name "/_B_ENC3") (class "Default")
      (node (ref "ENC4") (pin "B") (pinfunction "B_B") (pintype "passive"))
      (node (ref "R32") (pin "1") (pinfunction "1_1") (pintype "passive"))
    )
    (net (code "151") (name "/_B_ENC4") (class "Default")
      (node (ref "ENC5") (pin "B") (pinfunction "B_B") (pintype "passive"))
      (node (ref "R33") (pin "1") (pinfunction "1_1") (pintype "passive"))
    )
    (net (code "152") (name "/_B_ENC5") (class "Default")
      (node (ref "ENC3") (pin "B") (pinfunction "B_B") (pintype "passive"))
      (node (ref "R31") (pin "1") (pinfunction "1_1") (pintype "passive"))
    )
    (net (code "168") (name "GND") (class "Default")
      (node (ref "C1") (pin "1") (pinfunction "1_1") (pintype "passive"))
      (node (ref "C10") (pin "2") (pinfunction "2_2") (pintype "passive"))
      (node (ref "C11") (pin "1") (pinfunction "1_1") (pintype "passive"))
      (node (ref "C2") (pin "1") (pinfunction "1_1") (pintype "passive"))
      (node (ref "C3") (pin "1") (pinfunction "1_1") (pintype "passive"))
      (node (ref "C4") (pin "1") (pinfunction "1_1") (pintype "passive"))
      (node (ref "C5") (pin "1") (pinfunction "1_1") (pintype "passive"))
      (node (ref "C6") (pin "1") (pinfunction "1_1") (pintype "passive"))
      (node (ref "C7") (pin "1") (pinfunction "1_1") (pintype "passive"))
      (node (ref "C8") (pin "1") (pinfunction "1_1") (pintype "passive"))
      (node (ref "C9") (pin "2") (pinfunction "2_2") (pintype "passive"))
      (node (ref "ENC1") (pin "2") (pinfunction "2_2") (pintype "passive"))
      (node (ref "ENC1") (pin "C") (pinfunction "C_C") (pintype "passive"))
      (node (ref "ENC2") (pin "2") (pinfunction "2_2") (pintype "passive"))
      (node (ref "ENC2") (pin "C") (pinfunction "C_C") (pintype "passive"))
      (node (ref "ENC3") (pin "2") (pinfunction "2_2") (pintype "passive"))
      (node (ref "ENC3") (pin "C") (pinfunction "C_C") (pintype "passive"))
      (node (ref "ENC4") (pin "2") (pinfunction "2_2") (pintype "passive"))
      (node (ref "ENC4") (pin "C") (pinfunction "C_C") (pintype "passive"))
      (node (ref "ENC5") (pin "2") (pinfunction "2_2") (pintype "passive"))
      (node (ref "ENC5") (pin "C") (pinfunction "C_C") (pintype "passive"))
      (node (ref "H1") (pin "6") (pinfunction "6_6") (pintype "passive"))
      (node (ref "IC1") (pin "13") (pinfunction "~{G}_13") (pintype "passive"))
      (node (ref "IC1") (pin "8") (pinfunction "GND_8") (pintype "passive"))
      (node (ref "IC2") (pin "10") (pinfunction "GND_10") (pintype "passive"))
      (node (ref "IC2") (pin "19") (pinfunction "~{OE}_19") (pintype "passive"))
      (node (ref "IC3") (pin "13") (pinfunction "~{G}_13") (pintype "passive"))
      (node (ref "IC3") (pin "8") (pinfunction "GND_8") (pintype "passive"))
      (node (ref "IC4") (pin "15") (pinfunction "Y0_15") (pintype "passive"))
      (node (ref "IC4") (pin "8") (pinfunction "GND_8") (pintype "passive"))
      (node (ref "IC5") (pin "15") (pinfunction "Y0_15") (pintype "passive"))
      (node (ref "IC5") (pin "8") (pinfunction "GND_8") (pintype "passive"))
      (node (ref "IC6") (pin "15") (pinfunction "Y0_15") (pintype "passive"))
      (node (ref "IC6") (pin "8") (pinfunction "GND_8") (pintype "passive"))
      (node (ref "IC7") (pin "1") (pinfunction "GND_1") (pintype "input"))
      (node (ref "IC9") (pin "2") (pinfunction "GND_2") (pintype "passive"))
      (node (ref "J1") (pin "15") (pinfunction "15_15") (pintype "passive"))
      (node (ref "J1") (pin "17") (pinfunction "17_17") (pintype "passive"))
      (node (ref "J1") (pin "19") (pinfunction "19_19") (pintype "passive"))
      (node (ref "J1") (pin "20") (pinfunction "20_20") (pintype "passive"))
      (node (ref "J1") (pin "21") (pinfunction "21_21") (pintype "passive"))
      (node (ref "J1") (pin "22") (pinfunction "22_22") (pintype "passive"))
      (node (ref "J1") (pin "23") (pinfunction "23_23") (pintype "passive"))
      (node (ref "J1") (pin "24") (pinfunction "24_24") (pintype "passive"))
      (node (ref "J1") (pin "25") (pinfunction "25_25") (pintype "passive"))
      (node (ref "J2") (pin "10") (pinfunction "GND_2_10") (pintype "passive"))
      (node (ref "J2") (pin "12") (pinfunction "DETECT1_12") (pintype "bidirectional"))
      (node (ref "J2") (pin "6") (pinfunction "VSS_6") (pintype "power_in"))
      (node (ref "J2") (pin "9") (pinfunction "GND_1_9") (pintype "passive"))
      (node (ref "J3") (pin "A1B12") (pinfunction "GND_A1B12") (pintype "power_in"))
      (node (ref "J3") (pin "B1A12") (pinfunction "GND_B1A12") (pintype "power_in"))
      (node (ref "J5") (pin "17") (pinfunction "17_17") (pintype "passive"))
      (node (ref "J5") (pin "19") (pinfunction "19_19") (pintype "passive"))
      (node (ref "J5") (pin "21") (pinfunction "21_21") (pintype "passive"))
      (node (ref "J5") (pin "23") (pinfunction "23_23") (pintype "passive"))
      (node (ref "J5") (pin "25") (pinfunction "25_25") (pintype "passive"))
      (node (ref "J5") (pin "27") (pinfunction "27_27") (pintype "passive"))
      (node (ref "LED1") (pin "3") (pinfunction "cathode_3") (pintype "passive"))
      (node (ref "LED2") (pin "3") (pinfunction "cathode_3") (pintype "passive"))
      (node (ref "LED3") (pin "3") (pinfunction "cathode_3") (pintype "passive"))
      (node (ref "LED4") (pin "3") (pinfunction "cathode_3") (pintype "passive"))
      (node (ref "LED5") (pin "3") (pinfunction "cathode_3") (pintype "passive"))
      (node (ref "R1") (pin "2") (pinfunction "2_2") (pintype "passive"))
      (node (ref "R21") (pin "1") (pinfunction "1_1") (pintype "passive"))
      (node (ref "R37") (pin "3") (pinfunction "3_3") (pintype "passive"))
      (node (ref "R41") (pin "1") (pinfunction "1_1") (pintype "passive"))
      (node (ref "SW1") (pin "2") (pinfunction "2_2") (pintype "passive"))
      (node (ref "SW2") (pin "2") (pinfunction "2_2") (pintype "passive"))
      (node (ref "SW3") (pin "2") (pinfunction "2_2") (pintype "passive"))
      (node (ref "SW4") (pin "2") (pinfunction "2_2") (pintype "passive"))
      (node (ref "SW5") (pin "2") (pinfunction "2_2") (pintype "passive"))
      (node (ref "SW8") (pin "2") (pinfunction "2_2") (pintype "passive"))
      (node (ref "SW9") (pin "2") (pinfunction "2_2") (pintype "passive"))
      (node (ref "U1") (pin "2") (pinfunction "2_2") (pintype "power_in"))
      (node (ref "VD1") (pin "2") (pinfunction "C_2") (pintype "passive"))
    )
    (net (code "169") (name "Net-(C3-Pad2)") (class "Default")
      (node (ref "C3") (pin "2") (pinfunction "2_2") (pintype "passive"))
      (node (ref "J3") (pin "S1") (pinfunction "SHIELD_S1") (pintype "passive"))
      (node (ref "J3") (pin "S2") (pinfunction "SHIELD_S2") (pintype "passive"))
      (node (ref "J3") (pin "S3") (pinfunction "SHIELD_S3") (pintype "passive"))
      (node (ref "J3") (pin "S4") (pinfunction "SHIELD_S4") (pintype "passive"))
      (node (ref "R21") (pin "2") (pinfunction "2_2") (pintype "passive"))
    )
    (net (code "170") (name "Net-(FL1-Pad1)") (class "Default")
      (node (ref "FL1") (pin "1") (pinfunction "1_1") (pintype "passive"))
      (node (ref "U1") (pin "6") (pinfunction "6_6") (pintype "bidirectional"))
    )
    (net (code "171") (name "Net-(FL1-Pad2)") (class "Default")
      (node (ref "FL1") (pin "2") (pinfunction "2_2") (pintype "passive"))
      (node (ref "U1") (pin "4") (pinfunction "4_4") (pintype "bidirectional"))
    )
    (net (code "172") (name "Net-(FL1-Pad3)") (class "Default")
      (node (ref "FL1") (pin "3") (pinfunction "3_3") (pintype "passive"))
      (node (ref "R20") (pin "2") (pinfunction "2_2") (pintype "passive"))
    )
    (net (code "173") (name "Net-(FL1-Pad4)") (class "Default")
      (node (ref "FL1") (pin "4") (pinfunction "4_4") (pintype "passive"))
      (node (ref "R18") (pin "2") (pinfunction "2_2") (pintype "passive"))
    )
    (net (code "174") (name "Net-(IC1-QA)") (class "Default")
      (node (ref "IC1") (pin "15") (pinfunction "QA_15") (pintype "passive"))
      (node (ref "R3") (pin "8") (pinfunction "8_8") (pintype "passive"))
    )
    (net (code "175") (name "Net-(IC1-QB)") (class "Default")
      (node (ref "IC1") (pin "1") (pinfunction "QB_1") (pintype "passive"))
      (node (ref "R3") (pin "7") (pinfunction "7_7") (pintype "passive"))
    )
    (net (code "176") (name "Net-(IC1-QC)") (class "Default")
      (node (ref "IC1") (pin "2") (pinfunction "QC_2") (pintype "passive"))
      (node (ref "R3") (pin "6") (pinfunction "6_6") (pintype "passive"))
    )
    (net (code "177") (name "Net-(IC1-QD)") (class "Default")
      (node (ref "IC1") (pin "3") (pinfunction "QD_3") (pintype "passive"))
      (node (ref "R3") (pin "5") (pinfunction "5_5") (pintype "passive"))
    )
    (net (code "178") (name "Net-(IC1-QE)") (class "Default")
      (node (ref "IC1") (pin "4") (pinfunction "QE_4") (pintype "passive"))
      (node (ref "R2") (pin "8") (pinfunction "8_8") (pintype "passive"))
    )
    (net (code "179") (name "Net-(IC1-QF)") (class "Default")
      (node (ref "IC1") (pin "5") (pinfunction "QF_5") (pintype "passive"))
      (node (ref "R2") (pin "7") (pinfunction "7_7") (pintype "passive"))
    )
    (net (code "180") (name "Net-(IC1-QG)") (class "Default")
      (node (ref "IC1") (pin "6") (pinfunction "QG_6") (pintype "passive"))
      (node (ref "R2") (pin "6") (pinfunction "6_6") (pintype "passive"))
    )
    (net (code "181") (name "Net-(IC1-QH')") (class "Default")
      (node (ref "IC1") (pin "9") (pinfunction "QH'_9") (pintype "passive"))
      (node (ref "IC3") (pin "14") (pinfunction "SI_14") (pintype "passive"))
    )
    (net (code "182") (name "Net-(IC1-QH)") (class "Default")
      (node (ref "IC1") (pin "7") (pinfunction "QH_7") (pintype "passive"))
      (node (ref "R2") (pin "5") (pinfunction "5_5") (pintype "passive"))
    )
    (net (code "183") (name "Net-(IC2-B4)") (class "Default")
      (node (ref "IC2") (pin "15") (pinfunction "B4_15") (pintype "passive"))
      (node (ref "R4") (pin "2") (pinfunction "2_2") (pintype "passive"))
    )
    (net (code "184") (name "Net-(IC3-QA)") (class "Default")
      (node (ref "IC3") (pin "15") (pinfunction "QA_15") (pintype "passive"))
      (node (ref "R6") (pin "8") (pinfunction "8_8") (pintype "passive"))
    )
    (net (code "185") (name "Net-(IC3-QB)") (class "Default")
      (node (ref "IC3") (pin "1") (pinfunction "QB_1") (pintype "passive"))
      (node (ref "R6") (pin "7") (pinfunction "7_7") (pintype "passive"))
    )
    (net (code "186") (name "Net-(IC3-QC)") (class "Default")
      (node (ref "IC3") (pin "2") (pinfunction "QC_2") (pintype "passive"))
      (node (ref "R6") (pin "6") (pinfunction "6_6") (pintype "passive"))
    )
    (net (code "187") (name "Net-(IC3-QD)") (class "Default")
      (node (ref "IC3") (pin "3") (pinfunction "QD_3") (pintype "passive"))
      (node (ref "R6") (pin "5") (pinfunction "5_5") (pintype "passive"))
    )
    (net (code "188") (name "Net-(IC3-QE)") (class "Default")
      (node (ref "IC3") (pin "4") (pinfunction "QE_4") (pintype "passive"))
      (node (ref "R5") (pin "8") (pinfunction "8_8") (pintype "passive"))
    )
    (net (code "189") (name "Net-(IC3-QF)") (class "Default")
      (node (ref "IC3") (pin "5") (pinfunction "QF_5") (pintype "passive"))
      (node (ref "R5") (pin "7") (pinfunction "7_7") (pintype "passive"))
    )
    (net (code "190") (name "Net-(IC3-QG)") (class "Default")
      (node (ref "IC3") (pin "6") (pinfunction "QG_6") (pintype "passive"))
      (node (ref "R5") (pin "6") (pinfunction "6_6") (pintype "passive"))
    )
    (net (code "191") (name "Net-(IC3-QH)") (class "Default")
      (node (ref "IC3") (pin "7") (pinfunction "QH_7") (pintype "passive"))
      (node (ref "R5") (pin "5") (pinfunction "5_5") (pintype "passive"))
    )
    (net (code "192") (name "Net-(IC4-Y5)") (class "Default")
      (node (ref "IC4") (pin "10") (pinfunction "Y5_10") (pintype "passive"))
      (node (ref "IC5") (pin "9") (pinfunction "Y6_9") (pintype "passive"))
    )
    (net (code "193") (name "Net-(IC5-Y5)") (class "Default")
      (node (ref "IC5") (pin "10") (pinfunction "Y5_10") (pintype "passive"))
      (node (ref "IC6") (pin "9") (pinfunction "Y6_9") (pintype "passive"))
    )
    (net (code "194") (name "Net-(IC9-FB)") (class "Default")
      (node (ref "IC9") (pin "3") (pinfunction "FB_3") (pintype "passive"))
      (node (ref "R40") (pin "1") (pinfunction "1_1") (pintype "passive"))
      (node (ref "R41") (pin "2") (pinfunction "2_2") (pintype "passive"))
    )
    (net (code "195") (name "Net-(IC9-SW)") (class "Default")
      (node (ref "D1") (pin "1") (pinfunction "1_1") (pintype "passive"))
      (node (ref "IC9") (pin "1") (pinfunction "SW_1") (pintype "passive"))
      (node (ref "L1") (pin "1") (pinfunction "1_1") (pintype "passive"))
    )
    (net (code "196") (name "Net-(J3-VBUS-PadA4B9)") (class "Default")
      (node (ref "J3") (pin "A4B9") (pinfunction "VBUS_A4B9") (pintype "power_in"))
      (node (ref "J3") (pin "B4A9") (pinfunction "VBUS_B4A9") (pintype "power_in"))
      (node (ref "R17") (pin "2") (pinfunction "2_2") (pintype "passive"))
      (node (ref "R19") (pin "1") (pinfunction "1_1") (pintype "passive"))
    )
    (net (code "197") (name "Net-(R19-Pad2)") (class "Default")
      (node (ref "R19") (pin "2") (pinfunction "2_2") (pintype "passive"))
      (node (ref "U1") (pin "5") (pinfunction "5_5") (pintype "power_in"))
    )
    (net (code "198") (name "V_USB") (class "Default")
      (node (ref "C2") (pin "2") (pinfunction "2_2") (pintype "passive"))
      (node (ref "C6") (pin "2") (pinfunction "2_2") (pintype "passive"))
      (node (ref "C9") (pin "1") (pinfunction "1_1") (pintype "passive"))
      (node (ref "IC9") (pin "4") (pinfunction "EN_4") (pintype "passive"))
      (node (ref "IC9") (pin "5") (pinfunction "IN_5") (pintype "passive"))
      (node (ref "L1") (pin "2") (pinfunction "2_2") (pintype "passive"))
      (node (ref "R11") (pin "2") (pinfunction "2_2") (pintype "passive"))
      (node (ref "R17") (pin "1") (pinfunction "1_1") (pintype "passive"))
    )
    (net (code "199") (name "unconnected-(ENC1-PadMT1)") (class "Default")
      (node (ref "ENC1") (pin "MT1") (pinfunction "MT1_MT1") (pintype "passive"))
    )
    (net (code "200") (name "unconnected-(ENC1-PadMT2)") (class "Default")
      (node (ref "ENC1") (pin "MT2") (pinfunction "MT2_MT2") (pintype "passive"))
    )
    (net (code "201") (name "unconnected-(ENC2-PadMT1)") (class "Default")
      (node (ref "ENC2") (pin "MT1") (pinfunction "MT1_MT1") (pintype "passive"))
    )
    (net (code "202") (name "unconnected-(ENC2-PadMT2)") (class "Default")
      (node (ref "ENC2") (pin "MT2") (pinfunction "MT2_MT2") (pintype "passive"))
    )
    (net (code "203") (name "unconnected-(ENC3-PadMT1)") (class "Default")
      (node (ref "ENC3") (pin "MT1") (pinfunction "MT1_MT1") (pintype "passive"))
    )
    (net (code "204") (name "unconnected-(ENC3-PadMT2)") (class "Default")
      (node (ref "ENC3") (pin "MT2") (pinfunction "MT2_MT2") (pintype "passive"))
    )
    (net (code "205") (name "unconnected-(ENC4-PadMT1)") (class "Default")
      (node (ref "ENC4") (pin "MT1") (pinfunction "MT1_MT1") (pintype "passive"))
    )
    (net (code "206") (name "unconnected-(ENC4-PadMT2)") (class "Default")
      (node (ref "ENC4") (pin "MT2") (pinfunction "MT2_MT2") (pintype "passive"))
    )
    (net (code "207") (name "unconnected-(ENC5-PadMT1)") (class "Default")
      (node (ref "ENC5") (pin "MT1") (pinfunction "MT1_MT1") (pintype "passive"))
    )
    (net (code "208") (name "unconnected-(ENC5-PadMT2)") (class "Default")
      (node (ref "ENC5") (pin "MT2") (pinfunction "MT2_MT2") (pintype "passive"))
    )
    (net (code "209") (name "unconnected-(IC2-A5-Pad6)") (class "Default")
      (node (ref "IC2") (pin "6") (pinfunction "A5_6") (pintype "passive"))
    )
    (net (code "210") (name "unconnected-(IC2-A6-Pad7)") (class "Default")
      (node (ref "IC2") (pin "7") (pinfunction "A6_7") (pintype "passive"))
    )
    (net (code "211") (name "unconnected-(IC2-A7-Pad8)") (class "Default")
      (node (ref "IC2") (pin "8") (pinfunction "A7_8") (pintype "passive"))
    )
    (net (code "212") (name "unconnected-(IC2-A8-Pad9)") (class "Default")
      (node (ref "IC2") (pin "9") (pinfunction "A8_9") (pintype "passive"))
    )
    (net (code "213") (name "unconnected-(IC2-B5-Pad14)") (class "Default")
      (node (ref "IC2") (pin "14") (pinfunction "B5_14") (pintype "passive"))
    )
    (net (code "214") (name "unconnected-(IC2-B6-Pad13)") (class "Default")
      (node (ref "IC2") (pin "13") (pinfunction "B6_13") (pintype "passive"))
    )
    (net (code "215") (name "unconnected-(IC2-B7-Pad12)") (class "Default")
      (node (ref "IC2") (pin "12") (pinfunction "B7_12") (pintype "passive"))
    )
    (net (code "216") (name "unconnected-(IC2-B8-Pad11)") (class "Default")
      (node (ref "IC2") (pin "11") (pinfunction "B8_11") (pintype "passive"))
    )
    (net (code "217") (name "unconnected-(IC3-QH'-Pad9)") (class "Default")
      (node (ref "IC3") (pin "9") (pinfunction "QH'_9") (pintype "passive"))
    )
    (net (code "218") (name "unconnected-(IC4-Y7-Pad7)") (class "Default")
      (node (ref "IC4") (pin "7") (pinfunction "Y7_7") (pintype "passive"))
    )
    (net (code "219") (name "unconnected-(IC5-Y7-Pad7)") (class "Default")
      (node (ref "IC5") (pin "7") (pinfunction "Y7_7") (pintype "passive"))
    )
    (net (code "220") (name "unconnected-(IC6-Y5-Pad10)") (class "Default")
      (node (ref "IC6") (pin "10") (pinfunction "Y5_10") (pintype "passive"))
    )
    (net (code "221") (name "unconnected-(IC6-Y7-Pad7)") (class "Default")
      (node (ref "IC6") (pin "7") (pinfunction "Y7_7") (pintype "passive"))
    )
    (net (code "222") (name "unconnected-(IC9-NC-Pad6)") (class "Default")
      (node (ref "IC9") (pin "6") (pinfunction "NC_6") (pintype "passive"))
    )
    (net (code "223") (name "unconnected-(J1-Pad1)") (class "Default")
      (node (ref "J1") (pin "1") (pinfunction "1_1") (pintype "passive"))
    )
    (net (code "224") (name "unconnected-(J1-Pad2)") (class "Default")
      (node (ref "J1") (pin "2") (pinfunction "2_2") (pintype "passive"))
    )
    (net (code "225") (name "unconnected-(J1-Pad3)") (class "Default")
      (node (ref "J1") (pin "3") (pinfunction "3_3") (pintype "passive"))
    )
    (net (code "226") (name "unconnected-(J1-Pad4)") (class "Default")
      (node (ref "J1") (pin "4") (pinfunction "4_4") (pintype "passive"))
    )
    (net (code "227") (name "unconnected-(J1-Pad5)") (class "Default")
      (node (ref "J1") (pin "5") (pinfunction "5_5") (pintype "passive"))
    )
    (net (code "228") (name "unconnected-(J1-Pad6)") (class "Default")
      (node (ref "J1") (pin "6") (pinfunction "6_6") (pintype "passive"))
    )
    (net (code "229") (name "unconnected-(J1-Pad7)") (class "Default")
      (node (ref "J1") (pin "7") (pinfunction "7_7") (pintype "passive"))
    )
    (net (code "230") (name "unconnected-(J1-Pad8)") (class "Default")
      (node (ref "J1") (pin "8") (pinfunction "8_8") (pintype "passive"))
    )
    (net (code "231") (name "unconnected-(J1-Pad9)") (class "Default")
      (node (ref "J1") (pin "9") (pinfunction "9_9") (pintype "passive"))
    )
    (net (code "232") (name "unconnected-(J1-Pad10)") (class "Default")
      (node (ref "J1") (pin "10") (pinfunction "10_10") (pintype "passive"))
    )
    (net (code "233") (name "unconnected-(J1-Pad11)") (class "Default")
      (node (ref "J1") (pin "11") (pinfunction "11_11") (pintype "passive"))
    )
    (net (code "234") (name "unconnected-(J1-Pad12)") (class "Default")
      (node (ref "J1") (pin "12") (pinfunction "12_12") (pintype "passive"))
    )
    (net (code "235") (name "unconnected-(J1-Pad13)") (class "Default")
      (node (ref "J1") (pin "13") (pinfunction "13_13") (pintype "passive"))
    )
    (net (code "236") (name "unconnected-(J1-Pad14)") (class "Default")
      (node (ref "J1") (pin "14") (pinfunction "14_14") (pintype "passive"))
    )
    (net (code "237") (name "unconnected-(J1-Pad16)") (class "Default")
      (node (ref "J1") (pin "16") (pinfunction "16_16") (pintype "passive"))
    )
    (net (code "238") (name "unconnected-(J1-Pad18)") (class "Default")
      (node (ref "J1") (pin "18") (pinfunction "18_18") (pintype "passive"))
    )
    (net (code "239") (name "unconnected-(J2-SHIELD-PadMP1)") (class "Default")
      (node (ref "J2") (pin "MP1") (pinfunction "SHIELD_MP1") (pintype "passive"))
    )
    (net (code "240") (name "unconnected-(J2-SHIELD-PadMP2)") (class "Default")
      (node (ref "J2") (pin "MP2") (pinfunction "SHIELD_MP2") (pintype "passive"))
    )
    (net (code "241") (name "unconnected-(J2-SHIELD-PadMP3)") (class "Default")
      (node (ref "J2") (pin "MP3") (pinfunction "SHIELD_MP3") (pintype "passive"))
    )
    (net (code "242") (name "unconnected-(J2-SHIELD-PadMP4)") (class "Default")
      (node (ref "J2") (pin "MP4") (pinfunction "SHIELD_MP4") (pintype "passive"))
    )
    (net (code "243") (name "unconnected-(J3-CC1-PadA5)") (class "Default")
      (node (ref "J3") (pin "A5") (pinfunction "CC1_A5") (pintype "bidirectional"))
    )
    (net (code "244") (name "unconnected-(J3-CC2-PadB5)") (class "Default")
      (node (ref "J3") (pin "B5") (pinfunction "CC2_B5") (pintype "bidirectional"))
    )
    (net (code "245") (name "unconnected-(J3-SBU1-PadA8)") (class "Default")
      (node (ref "J3") (pin "A8") (pinfunction "SBU1_A8") (pintype "bidirectional"))
    )
    (net (code "246") (name "unconnected-(J3-SBU2-PadB8)") (class "Default")
      (node (ref "J3") (pin "B8") (pinfunction "SBU2_B8") (pintype "bidirectional"))
    )
    (net (code "247") (name "unconnected-(J4-4-Pad6)") (class "Default")
      (node (ref "J4") (pin "6") (pinfunction "4_6") (pintype "passive"))
    )
    (net (code "248") (name "unconnected-(J7-4-Pad6)") (class "Default")
      (node (ref "J7") (pin "6") (pinfunction "4_6") (pintype "passive"))
    )
    (net (code "249") (name "unconnected-(J8-Pad1)") (class "Default")
      (node (ref "J8") (pin "1") (pinfunction "1_1") (pintype "passive"))
    )
    (net (code "250") (name "unconnected-(J8-Pad2)") (class "Default")
      (node (ref "J8") (pin "2") (pinfunction "2_2") (pintype "passive"))
    )
    (net (code "251") (name "unconnected-(J8-Pad3)") (class "Default")
      (node (ref "J8") (pin "3") (pinfunction "3_3") (pintype "passive"))
    )
    (net (code "252") (name "unconnected-(J8-Pad4)") (class "Default")
      (node (ref "J8") (pin "4") (pinfunction "4_4") (pintype "passive"))
    )
    (net (code "253") (name "unconnected-(J8-Pad5)") (class "Default")
      (node (ref "J8") (pin "5") (pinfunction "5_5") (pintype "passive"))
    )
    (net (code "254") (name "unconnected-(J8-Pad6)") (class "Default")
      (node (ref "J8") (pin "6") (pinfunction "6_6") (pintype "passive"))
    )
    (net (code "255") (name "unconnected-(J8-Pad7)") (class "Default")
      (node (ref "J8") (pin "7") (pinfunction "7_7") (pintype "passive"))
    )
    (net (code "256") (name "unconnected-(J8-Pad8)") (class "Default")
      (node (ref "J8") (pin "8") (pinfunction "8_8") (pintype "passive"))
    )
    (net (code "257") (name "unconnected-(J8-Pad9)") (class "Default")
      (node (ref "J8") (pin "9") (pinfunction "9_9") (pintype "passive"))
    )
    (net (code "258") (name "unconnected-(J8-Pad10)") (class "Default")
      (node (ref "J8") (pin "10") (pinfunction "10_10") (pintype "passive"))
    )
    (net (code "259") (name "unconnected-(J8-Pad11)") (class "Default")
      (node (ref "J8") (pin "11") (pinfunction "11_11") (pintype "passive"))
    )
    (net (code "260") (name "unconnected-(J8-Pad12)") (class "Default")
      (node (ref "J8") (pin "12") (pinfunction "12_12") (pintype "passive"))
    )
    (net (code "261") (name "unconnected-(J8-Pad13)") (class "Default")
      (node (ref "J8") (pin "13") (pinfunction "13_13") (pintype "passive"))
    )
    (net (code "262") (name "unconnected-(J8-Pad14)") (class "Default")
      (node (ref "J8") (pin "14") (pinfunction "14_14") (pintype "passive"))
    )
    (net (code "263") (name "unconnected-(J8-Pad15)") (class "Default")
      (node (ref "J8") (pin "15") (pinfunction "15_15") (pintype "passive"))
    )
    (net (code "264") (name "unconnected-(J8-Pad16)") (class "Default")
      (node (ref "J8") (pin "16") (pinfunction "16_16") (pintype "passive"))
    )
    (net (code "265") (name "unconnected-(J8-Pad17)") (class "Default")
      (node (ref "J8") (pin "17") (pinfunction "17_17") (pintype "passive"))
    )
    (net (code "266") (name "unconnected-(J8-Pad18)") (class "Default")
      (node (ref "J8") (pin "18") (pinfunction "18_18") (pintype "passive"))
    )
    (net (code "267") (name "unconnected-(J8-Pad19)") (class "Default")
      (node (ref "J8") (pin "19") (pinfunction "19_19") (pintype "passive"))
    )
    (net (code "268") (name "unconnected-(J8-Pad20)") (class "Default")
      (node (ref "J8") (pin "20") (pinfunction "20_20") (pintype "passive"))
    )
    (net (code "269") (name "unconnected-(J8-Pad21)") (class "Default")
      (node (ref "J8") (pin "21") (pinfunction "21_21") (pintype "passive"))
    )
    (net (code "270") (name "unconnected-(J8-Pad22)") (class "Default")
      (node (ref "J8") (pin "22") (pinfunction "22_22") (pintype "passive"))
    )
    (net (code "271") (name "unconnected-(J8-Pad23)") (class "Default")
      (node (ref "J8") (pin "23") (pinfunction "23_23") (pintype "passive"))
    )
    (net (code "272") (name "unconnected-(J8-Pad24)") (class "Default")
      (node (ref "J8") (pin "24") (pinfunction "24_24") (pintype "passive"))
    )
    (net (code "273") (name "unconnected-(J8-Pad25)") (class "Default")
      (node (ref "J8") (pin "25") (pinfunction "25_25") (pintype "passive"))
    )
    (net (code "274") (name "unconnected-(J8-Pad26)") (class "Default")
      (node (ref "J8") (pin "26") (pinfunction "26_26") (pintype "passive"))
    )
    (net (code "275") (name "unconnected-(J8-Pad27)") (class "Default")
      (node (ref "J8") (pin "27") (pinfunction "27_27") (pintype "passive"))
    )
    (net (code "276") (name "unconnected-(J8-Pad28)") (class "Default")
      (node (ref "J8") (pin "28") (pinfunction "28_28") (pintype "passive"))
    )
    (net (code "277") (name "unconnected-(J8-Pad29)") (class "Default")
      (node (ref "J8") (pin "29") (pinfunction "29_29") (pintype "passive"))
    )
    (net (code "278") (name "unconnected-(J8-Pad30)") (class "Default")
      (node (ref "J8") (pin "30") (pinfunction "30_30") (pintype "passive"))
    )
    (net (code "279") (name "unconnected-(J8-Pad31)") (class "Default")
      (node (ref "J8") (pin "31") (pinfunction "31_31") (pintype "passive"))
    )
    (net (code "280") (name "unconnected-(J8-Pad32)") (class "Default")
      (node (ref "J8") (pin "32") (pinfunction "32_32") (pintype "passive"))
    )
    (net (code "281") (name "unconnected-(J8-Pad33)") (class "Default")
      (node (ref "J8") (pin "33") (pinfunction "33_33") (pintype "passive"))
    )
    (net (code "282") (name "unconnected-(J8-Pad34)") (class "Default")
      (node (ref "J8") (pin "34") (pinfunction "34_34") (pintype "passive"))
    )
    (net (code "283") (name "unconnected-(J8-Pad35)") (class "Default")
      (node (ref "J8") (pin "35") (pinfunction "35_35") (pintype "passive"))
    )
    (net (code "284") (name "unconnected-(J8-Pad36)") (class "Default")
      (node (ref "J8") (pin "36") (pinfunction "36_36") (pintype "passive"))
    )
    (net (code "285") (name "unconnected-(J8-Pad37)") (class "Default")
      (node (ref "J8") (pin "37") (pinfunction "37_37") (pintype "passive"))
    )
    (net (code "286") (name "unconnected-(J8-Pad38)") (class "Default")
      (node (ref "J8") (pin "38") (pinfunction "38_38") (pintype "passive"))
    )
    (net (code "287") (name "unconnected-(J8-Pad39)") (class "Default")
      (node (ref "J8") (pin "39") (pinfunction "39_39") (pintype "passive"))
    )
    (net (code "288") (name "unconnected-(J8-Pad40)") (class "Default")
      (node (ref "J8") (pin "40") (pinfunction "40_40") (pintype "passive"))
    )
    (net (code "289") (name "unconnected-(J8-Pad41)") (class "Default")
      (node (ref "J8") (pin "41") (pinfunction "41_41") (pintype "passive"))
    )
    (net (code "290") (name "unconnected-(R37-Pad4)") (class "Default")
      (node (ref "R37") (pin "4") (pinfunction "4_4") (pintype "passive"))
    )
  )
)
